# SM3320-BATT-EV.net
KiCad netlist of a schematic drawn in Altium Designer
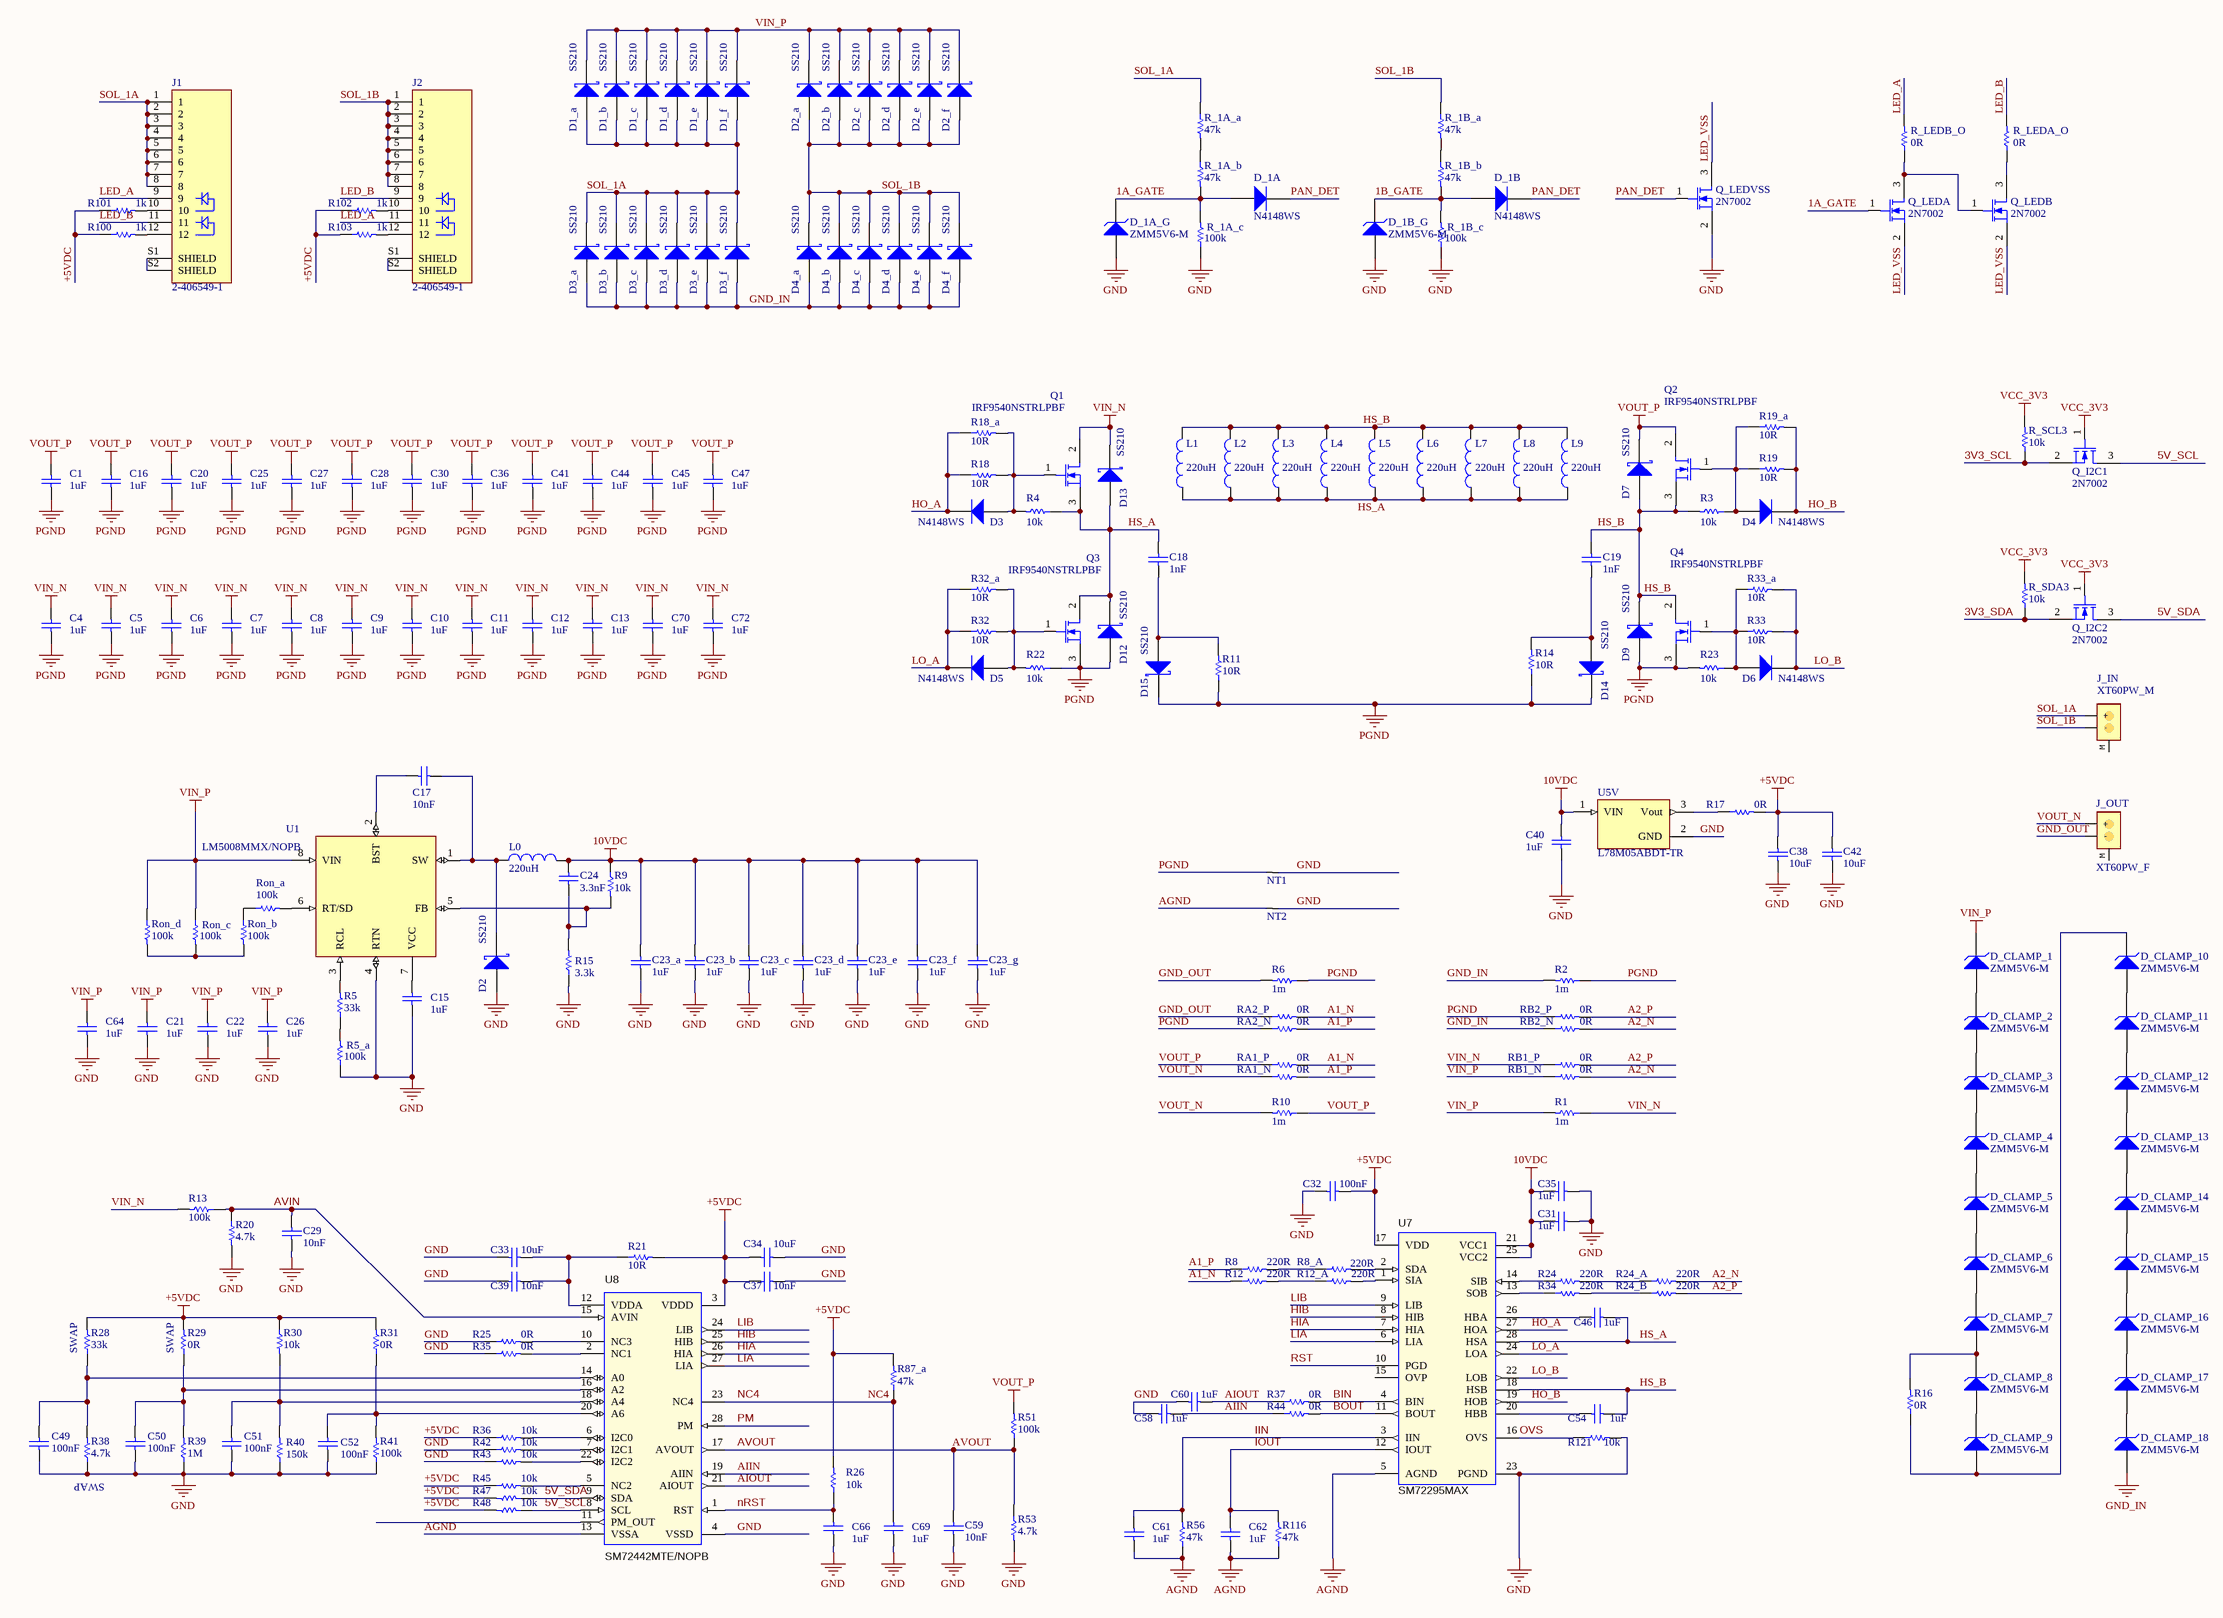
[diagram p0: SM3320-BATT-EV.SchDoc]

(export (version "E")
  (design (tool "Eeschema 10.0.6"))
  (components
    (comp (ref "C1")
      (value "1uF")
      (footprint "C_1206")
      (description "C - CAPACITOR - MLCC - 1uF - 100V - 1206 - X7R")
      (fields (field (name "LCSC PART #") "C91151") (field (name "Comment") "1206B105K101NT"))
      (libsource (lib "JLC_PCB") (part "1206B105K101NT"))
    )
    (comp (ref "C4")
      (value "1uF")
      (footprint "C_1206")
      (description "C - CAPACITOR - MLCC - 1uF - 100V - 1206 - X7R")
      (fields (field (name "LCSC PART #") "C91151") (field (name "Comment") "1206B105K101NT"))
      (libsource (lib "JLC_PCB") (part "1206B105K101NT"))
    )
    (comp (ref "C5")
      (value "1uF")
      (footprint "C_1206")
      (description "C - CAPACITOR - MLCC - 1uF - 100V - 1206 - X7R")
      (fields (field (name "LCSC PART #") "C91151") (field (name "Comment") "1206B105K101NT"))
      (libsource (lib "JLC_PCB") (part "1206B105K101NT"))
    )
    (comp (ref "C6")
      (value "1uF")
      (footprint "C_1206")
      (description "C - CAPACITOR - MLCC - 1uF - 100V - 1206 - X7R")
      (fields (field (name "LCSC PART #") "C91151") (field (name "Comment") "1206B105K101NT"))
      (libsource (lib "JLC_PCB") (part "1206B105K101NT"))
    )
    (comp (ref "C7")
      (value "1uF")
      (footprint "C_1206")
      (description "C - CAPACITOR - MLCC - 1uF - 100V - 1206 - X7R")
      (fields (field (name "LCSC PART #") "C91151") (field (name "Comment") "1206B105K101NT"))
      (libsource (lib "JLC_PCB") (part "1206B105K101NT"))
    )
    (comp (ref "C8")
      (value "1uF")
      (footprint "C_1206")
      (description "C - CAPACITOR - MLCC - 1uF - 100V - 1206 - X7R")
      (fields (field (name "LCSC PART #") "C91151") (field (name "Comment") "1206B105K101NT"))
      (libsource (lib "JLC_PCB") (part "1206B105K101NT"))
    )
    (comp (ref "C9")
      (value "1uF")
      (footprint "C_1206")
      (description "C - CAPACITOR - MLCC - 1uF - 100V - 1206 - X7R")
      (fields (field (name "LCSC PART #") "C91151") (field (name "Comment") "1206B105K101NT"))
      (libsource (lib "JLC_PCB") (part "1206B105K101NT"))
    )
    (comp (ref "C10")
      (value "1uF")
      (footprint "C_1206")
      (description "C - CAPACITOR - MLCC - 1uF - 100V - 1206 - X7R")
      (fields (field (name "LCSC PART #") "C91151") (field (name "Comment") "1206B105K101NT"))
      (libsource (lib "JLC_PCB") (part "1206B105K101NT"))
    )
    (comp (ref "C11")
      (value "1uF")
      (footprint "C_1206")
      (description "C - CAPACITOR - MLCC - 1uF - 100V - 1206 - X7R")
      (fields (field (name "LCSC PART #") "C91151") (field (name "Comment") "1206B105K101NT"))
      (libsource (lib "JLC_PCB") (part "1206B105K101NT"))
    )
    (comp (ref "C12")
      (value "1uF")
      (footprint "C_1206")
      (description "C - CAPACITOR - MLCC - 1uF - 100V - 1206 - X7R")
      (fields (field (name "LCSC PART #") "C91151") (field (name "Comment") "1206B105K101NT"))
      (libsource (lib "JLC_PCB") (part "1206B105K101NT"))
    )
    (comp (ref "C13")
      (value "1uF")
      (footprint "C_1206")
      (description "C - CAPACITOR - MLCC - 1uF - 100V - 1206 - X7R")
      (fields (field (name "LCSC PART #") "C91151") (field (name "Comment") "1206B105K101NT"))
      (libsource (lib "JLC_PCB") (part "1206B105K101NT"))
    )
    (comp (ref "C15")
      (value "1uF")
      (footprint "C_0402")
      (description "C - CAPACITOR - MLCC - 1uF - 25V - 0402")
      (fields (field (name "LCSC PART #") "C52923") (field (name "Comment") "CL05A105KA5NQNC"))
      (libsource (lib "JLC_PCB") (part "CL05A105KA5NQNC"))
    )
    (comp (ref "C16")
      (value "1uF")
      (footprint "C_1206")
      (description "C - CAPACITOR - MLCC - 1uF - 100V - 1206 - X7R")
      (fields (field (name "LCSC PART #") "C91151") (field (name "Comment") "1206B105K101NT"))
      (libsource (lib "JLC_PCB") (part "1206B105K101NT"))
    )
    (comp (ref "C17")
      (value "10nF")
      (footprint "C_0402")
      (description "C - CAPACITOR - MLCC - 10nF - 50V - 0402")
      (fields (field (name "LCSC PART #") "C15195") (field (name "Comment") "CL05B103KB5NNNC"))
      (libsource (lib "JLC_PCB") (part "CL05B103KB5NNNC"))
    )
    (comp (ref "C18")
      (value "1nF")
      (footprint "C_1206")
      (description "C - CAPACITOR - MLCC - 1nF - 2000V - 1206 - X7R")
      (fields (field (name "LCSC PART #") "C9196") (field (name "Comment") "1206B102K202NT"))
      (libsource (lib "JLC_PCB") (part "1206B102K202NT"))
    )
    (comp (ref "C19")
      (value "1nF")
      (footprint "C_1206")
      (description "C - CAPACITOR - MLCC - 1nF - 2000V - 1206 - X7R")
      (fields (field (name "LCSC PART #") "C9196") (field (name "Comment") "1206B102K202NT"))
      (libsource (lib "JLC_PCB") (part "1206B102K202NT"))
    )
    (comp (ref "C20")
      (value "1uF")
      (footprint "C_1206")
      (description "C - CAPACITOR - MLCC - 1uF - 100V - 1206 - X7R")
      (fields (field (name "LCSC PART #") "C91151") (field (name "Comment") "1206B105K101NT"))
      (libsource (lib "JLC_PCB") (part "1206B105K101NT"))
    )
    (comp (ref "C21")
      (value "1uF")
      (footprint "C_1206")
      (description "C - CAPACITOR - MLCC - 1uF - 100V - 1206 - X7R")
      (fields (field (name "LCSC PART #") "C91151") (field (name "Comment") "1206B105K101NT"))
      (libsource (lib "JLC_PCB") (part "1206B105K101NT"))
    )
    (comp (ref "C22")
      (value "1uF")
      (footprint "C_1206")
      (description "C - CAPACITOR - MLCC - 1uF - 100V - 1206 - X7R")
      (fields (field (name "LCSC PART #") "C91151") (field (name "Comment") "1206B105K101NT"))
      (libsource (lib "JLC_PCB") (part "1206B105K101NT"))
    )
    (comp (ref "C23_a")
      (value "1uF")
      (footprint "C_0402")
      (description "C - CAPACITOR - MLCC - 1uF - 25V - 0402")
      (fields (field (name "LCSC PART #") "C52923") (field (name "Comment") "CL05A105KA5NQNC"))
      (libsource (lib "JLC_PCB") (part "CL05A105KA5NQNC"))
    )
    (comp (ref "C23_b")
      (value "1uF")
      (footprint "C_0402")
      (description "C - CAPACITOR - MLCC - 1uF - 25V - 0402")
      (fields (field (name "LCSC PART #") "C52923") (field (name "Comment") "CL05A105KA5NQNC"))
      (libsource (lib "JLC_PCB") (part "CL05A105KA5NQNC"))
    )
    (comp (ref "C23_c")
      (value "1uF")
      (footprint "C_0402")
      (description "C - CAPACITOR - MLCC - 1uF - 25V - 0402")
      (fields (field (name "LCSC PART #") "C52923") (field (name "Comment") "CL05A105KA5NQNC"))
      (libsource (lib "JLC_PCB") (part "CL05A105KA5NQNC"))
    )
    (comp (ref "C23_d")
      (value "1uF")
      (footprint "C_0402")
      (description "C - CAPACITOR - MLCC - 1uF - 25V - 0402")
      (fields (field (name "LCSC PART #") "C52923") (field (name "Comment") "CL05A105KA5NQNC"))
      (libsource (lib "JLC_PCB") (part "CL05A105KA5NQNC"))
    )
    (comp (ref "C23_e")
      (value "1uF")
      (footprint "C_0402")
      (description "C - CAPACITOR - MLCC - 1uF - 25V - 0402")
      (fields (field (name "LCSC PART #") "C52923") (field (name "Comment") "CL05A105KA5NQNC"))
      (libsource (lib "JLC_PCB") (part "CL05A105KA5NQNC"))
    )
    (comp (ref "C23_f")
      (value "1uF")
      (footprint "C_0402")
      (description "C - CAPACITOR - MLCC - 1uF - 25V - 0402")
      (fields (field (name "LCSC PART #") "C52923") (field (name "Comment") "CL05A105KA5NQNC"))
      (libsource (lib "JLC_PCB") (part "CL05A105KA5NQNC"))
    )
    (comp (ref "C23_g")
      (value "1uF")
      (footprint "C_0402")
      (description "C - CAPACITOR - MLCC - 1uF - 25V - 0402")
      (fields (field (name "LCSC PART #") "C52923") (field (name "Comment") "CL05A105KA5NQNC"))
      (libsource (lib "JLC_PCB") (part "CL05A105KA5NQNC"))
    )
    (comp (ref "C24")
      (value "3.3nF")
      (footprint "C_0402")
      (description "C - CAPACITOR - MLCC - 3.3nF - 50V - 0402")
      (fields (field (name "LCSC PART #") "C26404") (field (name "Comment") "CL05B332KB5NNNC"))
      (libsource (lib "JLC_PCB") (part "CL05B332KB5NNNC"))
    )
    (comp (ref "C25")
      (value "1uF")
      (footprint "C_1206")
      (description "C - CAPACITOR - MLCC - 1uF - 100V - 1206 - X7R")
      (fields (field (name "LCSC PART #") "C91151") (field (name "Comment") "1206B105K101NT"))
      (libsource (lib "JLC_PCB") (part "1206B105K101NT"))
    )
    (comp (ref "C26")
      (value "1uF")
      (footprint "C_1206")
      (description "C - CAPACITOR - MLCC - 1uF - 100V - 1206 - X7R")
      (fields (field (name "LCSC PART #") "C91151") (field (name "Comment") "1206B105K101NT"))
      (libsource (lib "JLC_PCB") (part "1206B105K101NT"))
    )
    (comp (ref "C27")
      (value "1uF")
      (footprint "C_1206")
      (description "C - CAPACITOR - MLCC - 1uF - 100V - 1206 - X7R")
      (fields (field (name "LCSC PART #") "C91151") (field (name "Comment") "1206B105K101NT"))
      (libsource (lib "JLC_PCB") (part "1206B105K101NT"))
    )
    (comp (ref "C28")
      (value "1uF")
      (footprint "C_1206")
      (description "C - CAPACITOR - MLCC - 1uF - 100V - 1206 - X7R")
      (fields (field (name "LCSC PART #") "C91151") (field (name "Comment") "1206B105K101NT"))
      (libsource (lib "JLC_PCB") (part "1206B105K101NT"))
    )
    (comp (ref "C29")
      (value "10nF")
      (footprint "C_0402")
      (description "C - CAPACITOR - MLCC - 10nF - 50V - 0402")
      (fields (field (name "LCSC PART #") "C15195") (field (name "Comment") "CL05B103KB5NNNC"))
      (libsource (lib "JLC_PCB") (part "CL05B103KB5NNNC"))
    )
    (comp (ref "C30")
      (value "1uF")
      (footprint "C_1206")
      (description "C - CAPACITOR - MLCC - 1uF - 100V - 1206 - X7R")
      (fields (field (name "LCSC PART #") "C91151") (field (name "Comment") "1206B105K101NT"))
      (libsource (lib "JLC_PCB") (part "1206B105K101NT"))
    )
    (comp (ref "C31")
      (value "1uF")
      (footprint "C_0402")
      (description "C - CAPACITOR - MLCC - 1uF - 25V - 0402")
      (fields (field (name "LCSC PART #") "C52923") (field (name "Comment") "CL05A105KA5NQNC"))
      (libsource (lib "JLC_PCB") (part "CL05A105KA5NQNC"))
    )
    (comp (ref "C32")
      (value "100nF")
      (footprint "C_0402")
      (description "C - CAPACITOR - MLCC - 100nF - 16V - 0402")
      (fields (field (name "LCSC PART #") "C1525") (field (name "Comment") "CL05B104KO5NNNC"))
      (libsource (lib "JLC_PCB") (part "CL05B104KO5NNNC"))
    )
    (comp (ref "C33")
      (value "10uF")
      (footprint "C_0402")
      (description "C - CAPACITOR - MLCC - 10uF - 6.3V - 0402")
      (fields (field (name "LCSC PART #") "C15525") (field (name "Comment") "CL05A106MQ5NUNC"))
      (libsource (lib "JLC_PCB") (part "CL05A106MQ5NUNC"))
    )
    (comp (ref "C34")
      (value "10uF")
      (footprint "C_0402")
      (description "C - CAPACITOR - MLCC - 10uF - 6.3V - 0402")
      (fields (field (name "LCSC PART #") "C15525") (field (name "Comment") "CL05A106MQ5NUNC"))
      (libsource (lib "JLC_PCB") (part "CL05A106MQ5NUNC"))
    )
    (comp (ref "C35")
      (value "1uF")
      (footprint "C_0402")
      (description "C - CAPACITOR - MLCC - 1uF - 25V - 0402")
      (fields (field (name "LCSC PART #") "C52923") (field (name "Comment") "CL05A105KA5NQNC"))
      (libsource (lib "JLC_PCB") (part "CL05A105KA5NQNC"))
    )
    (comp (ref "C36")
      (value "1uF")
      (footprint "C_1206")
      (description "C - CAPACITOR - MLCC - 1uF - 100V - 1206 - X7R")
      (fields (field (name "LCSC PART #") "C91151") (field (name "Comment") "1206B105K101NT"))
      (libsource (lib "JLC_PCB") (part "1206B105K101NT"))
    )
    (comp (ref "C37")
      (value "10nF")
      (footprint "C_0402")
      (description "C - CAPACITOR - MLCC - 10nF - 50V - 0402")
      (fields (field (name "LCSC PART #") "C15195") (field (name "Comment") "CL05B103KB5NNNC"))
      (libsource (lib "JLC_PCB") (part "CL05B103KB5NNNC"))
    )
    (comp (ref "C38")
      (value "10uF")
      (footprint "C_0402")
      (description "C - CAPACITOR - MLCC - 10uF - 6.3V - 0402")
      (fields (field (name "LCSC PART #") "C15525") (field (name "Comment") "CL05A106MQ5NUNC"))
      (libsource (lib "JLC_PCB") (part "CL05A106MQ5NUNC"))
    )
    (comp (ref "C39")
      (value "10nF")
      (footprint "C_0402")
      (description "C - CAPACITOR - MLCC - 10nF - 50V - 0402")
      (fields (field (name "LCSC PART #") "C15195") (field (name "Comment") "CL05B103KB5NNNC"))
      (libsource (lib "JLC_PCB") (part "CL05B103KB5NNNC"))
    )
    (comp (ref "C40")
      (value "1uF")
      (footprint "C_0402")
      (description "C - CAPACITOR - MLCC - 1uF - 25V - 0402")
      (fields (field (name "LCSC PART #") "C52923") (field (name "Comment") "CL05A105KA5NQNC"))
      (libsource (lib "JLC_PCB") (part "CL05A105KA5NQNC"))
    )
    (comp (ref "C41")
      (value "1uF")
      (footprint "C_1206")
      (description "C - CAPACITOR - MLCC - 1uF - 100V - 1206 - X7R")
      (fields (field (name "LCSC PART #") "C91151") (field (name "Comment") "1206B105K101NT"))
      (libsource (lib "JLC_PCB") (part "1206B105K101NT"))
    )
    (comp (ref "C42")
      (value "10uF")
      (footprint "C_0402")
      (description "C - CAPACITOR - MLCC - 10uF - 6.3V - 0402")
      (fields (field (name "LCSC PART #") "C15525") (field (name "Comment") "CL05A106MQ5NUNC"))
      (libsource (lib "JLC_PCB") (part "CL05A106MQ5NUNC"))
    )
    (comp (ref "C44")
      (value "1uF")
      (footprint "C_1206")
      (description "C - CAPACITOR - MLCC - 1uF - 100V - 1206 - X7R")
      (fields (field (name "LCSC PART #") "C91151") (field (name "Comment") "1206B105K101NT"))
      (libsource (lib "JLC_PCB") (part "1206B105K101NT"))
    )
    (comp (ref "C45")
      (value "1uF")
      (footprint "C_1206")
      (description "C - CAPACITOR - MLCC - 1uF - 100V - 1206 - X7R")
      (fields (field (name "LCSC PART #") "C91151") (field (name "Comment") "1206B105K101NT"))
      (libsource (lib "JLC_PCB") (part "1206B105K101NT"))
    )
    (comp (ref "C46")
      (value "1uF")
      (footprint "C_0402")
      (description "C - CAPACITOR - MLCC - 1uF - 25V - 0402")
      (fields (field (name "LCSC PART #") "C52923") (field (name "Comment") "CL05A105KA5NQNC"))
      (libsource (lib "JLC_PCB") (part "CL05A105KA5NQNC"))
    )
    (comp (ref "C47")
      (value "1uF")
      (footprint "C_1206")
      (description "C - CAPACITOR - MLCC - 1uF - 100V - 1206 - X7R")
      (fields (field (name "LCSC PART #") "C91151") (field (name "Comment") "1206B105K101NT"))
      (libsource (lib "JLC_PCB") (part "1206B105K101NT"))
    )
    (comp (ref "C49")
      (value "100nF")
      (footprint "C_0402")
      (description "C - CAPACITOR - MLCC - 100nF - 16V - 0402")
      (fields (field (name "LCSC PART #") "C1525") (field (name "Comment") "CL05B104KO5NNNC"))
      (libsource (lib "JLC_PCB") (part "CL05B104KO5NNNC"))
    )
    (comp (ref "C50")
      (value "100nF")
      (footprint "C_0402")
      (description "C - CAPACITOR - MLCC - 100nF - 16V - 0402")
      (fields (field (name "LCSC PART #") "C1525") (field (name "Comment") "CL05B104KO5NNNC"))
      (libsource (lib "JLC_PCB") (part "CL05B104KO5NNNC"))
    )
    (comp (ref "C51")
      (value "100nF")
      (footprint "C_0402")
      (description "C - CAPACITOR - MLCC - 100nF - 16V - 0402")
      (fields (field (name "LCSC PART #") "C1525") (field (name "Comment") "CL05B104KO5NNNC"))
      (libsource (lib "JLC_PCB") (part "CL05B104KO5NNNC"))
    )
    (comp (ref "C52")
      (value "100nF")
      (footprint "C_0402")
      (description "C - CAPACITOR - MLCC - 100nF - 16V - 0402")
      (fields (field (name "LCSC PART #") "C1525") (field (name "Comment") "CL05B104KO5NNNC"))
      (libsource (lib "JLC_PCB") (part "CL05B104KO5NNNC"))
    )
    (comp (ref "C54")
      (value "1uF")
      (footprint "C_0402")
      (description "C - CAPACITOR - MLCC - 1uF - 25V - 0402")
      (fields (field (name "LCSC PART #") "C52923") (field (name "Comment") "CL05A105KA5NQNC"))
      (libsource (lib "JLC_PCB") (part "CL05A105KA5NQNC"))
    )
    (comp (ref "C58")
      (value "1uF")
      (footprint "C_0402")
      (description "C - CAPACITOR - MLCC - 1uF - 25V - 0402")
      (fields (field (name "LCSC PART #") "C52923") (field (name "Comment") "CL05A105KA5NQNC"))
      (libsource (lib "JLC_PCB") (part "CL05A105KA5NQNC"))
    )
    (comp (ref "C59")
      (value "10nF")
      (footprint "C_0402")
      (description "C - CAPACITOR - MLCC - 10nF - 50V - 0402")
      (fields (field (name "LCSC PART #") "C15195") (field (name "Comment") "CL05B103KB5NNNC"))
      (libsource (lib "JLC_PCB") (part "CL05B103KB5NNNC"))
    )
    (comp (ref "C60")
      (value "1uF")
      (footprint "C_0402")
      (description "C - CAPACITOR - MLCC - 1uF - 25V - 0402")
      (fields (field (name "LCSC PART #") "C52923") (field (name "Comment") "CL05A105KA5NQNC"))
      (libsource (lib "JLC_PCB") (part "CL05A105KA5NQNC"))
    )
    (comp (ref "C61")
      (value "1uF")
      (footprint "C_0402")
      (description "C - CAPACITOR - MLCC - 1uF - 25V - 0402")
      (fields (field (name "LCSC PART #") "C52923") (field (name "Comment") "CL05A105KA5NQNC"))
      (libsource (lib "JLC_PCB") (part "CL05A105KA5NQNC"))
    )
    (comp (ref "C62")
      (value "1uF")
      (footprint "C_0402")
      (description "C - CAPACITOR - MLCC - 1uF - 25V - 0402")
      (fields (field (name "LCSC PART #") "C52923") (field (name "Comment") "CL05A105KA5NQNC"))
      (libsource (lib "JLC_PCB") (part "CL05A105KA5NQNC"))
    )
    (comp (ref "C64")
      (value "1uF")
      (footprint "C_1206")
      (description "C - CAPACITOR - MLCC - 1uF - 100V - 1206 - X7R")
      (fields (field (name "LCSC PART #") "C91151") (field (name "Comment") "1206B105K101NT"))
      (libsource (lib "JLC_PCB") (part "1206B105K101NT"))
    )
    (comp (ref "C66")
      (value "1uF")
      (footprint "C_0402")
      (description "C - CAPACITOR - MLCC - 1uF - 25V - 0402")
      (fields (field (name "LCSC PART #") "C52923") (field (name "Comment") "CL05A105KA5NQNC"))
      (libsource (lib "JLC_PCB") (part "CL05A105KA5NQNC"))
    )
    (comp (ref "C69")
      (value "1uF")
      (footprint "C_0402")
      (description "C - CAPACITOR - MLCC - 1uF - 25V - 0402")
      (fields (field (name "LCSC PART #") "C52923") (field (name "Comment") "CL05A105KA5NQNC"))
      (libsource (lib "JLC_PCB") (part "CL05A105KA5NQNC"))
    )
    (comp (ref "C70")
      (value "1uF")
      (footprint "C_1206")
      (description "C - CAPACITOR - MLCC - 1uF - 100V - 1206 - X7R")
      (fields (field (name "LCSC PART #") "C91151") (field (name "Comment") "1206B105K101NT"))
      (libsource (lib "JLC_PCB") (part "1206B105K101NT"))
    )
    (comp (ref "C72")
      (value "1uF")
      (footprint "C_1206")
      (description "C - CAPACITOR - MLCC - 1uF - 100V - 1206 - X7R")
      (fields (field (name "LCSC PART #") "C91151") (field (name "Comment") "1206B105K101NT"))
      (libsource (lib "JLC_PCB") (part "1206B105K101NT"))
    )
    (comp (ref "D1_a")
      (value "SS210")
      (footprint "DO-214AC")
      (description "D - DIODE - SCHOTTKY - 100V - 2A")
      (fields (field (name "LCSC PART #") "C14996"))
      (libsource (lib "JLC_PCB") (part "SS210"))
    )
    (comp (ref "D1_b")
      (value "SS210")
      (footprint "DO-214AC")
      (description "D - DIODE - SCHOTTKY - 100V - 2A")
      (fields (field (name "LCSC PART #") "C14996"))
      (libsource (lib "JLC_PCB") (part "SS210"))
    )
    (comp (ref "D1_c")
      (value "SS210")
      (footprint "DO-214AC")
      (description "D - DIODE - SCHOTTKY - 100V - 2A")
      (fields (field (name "LCSC PART #") "C14996"))
      (libsource (lib "JLC_PCB") (part "SS210"))
    )
    (comp (ref "D1_d")
      (value "SS210")
      (footprint "DO-214AC")
      (description "D - DIODE - SCHOTTKY - 100V - 2A")
      (fields (field (name "LCSC PART #") "C14996"))
      (libsource (lib "JLC_PCB") (part "SS210"))
    )
    (comp (ref "D1_e")
      (value "SS210")
      (footprint "DO-214AC")
      (description "D - DIODE - SCHOTTKY - 100V - 2A")
      (fields (field (name "LCSC PART #") "C14996"))
      (libsource (lib "JLC_PCB") (part "SS210"))
    )
    (comp (ref "D1_f")
      (value "SS210")
      (footprint "DO-214AC")
      (description "D - DIODE - SCHOTTKY - 100V - 2A")
      (fields (field (name "LCSC PART #") "C14996"))
      (libsource (lib "JLC_PCB") (part "SS210"))
    )
    (comp (ref "D2")
      (value "SS210")
      (footprint "DO-214AC")
      (description "D - DIODE - SCHOTTKY - 100V - 2A")
      (fields (field (name "LCSC PART #") "C14996"))
      (libsource (lib "JLC_PCB") (part "SS210"))
    )
    (comp (ref "D2_a")
      (value "SS210")
      (footprint "DO-214AC")
      (description "D - DIODE - SCHOTTKY - 100V - 2A")
      (fields (field (name "LCSC PART #") "C14996"))
      (libsource (lib "JLC_PCB") (part "SS210"))
    )
    (comp (ref "D2_b")
      (value "SS210")
      (footprint "DO-214AC")
      (description "D - DIODE - SCHOTTKY - 100V - 2A")
      (fields (field (name "LCSC PART #") "C14996"))
      (libsource (lib "JLC_PCB") (part "SS210"))
    )
    (comp (ref "D2_c")
      (value "SS210")
      (footprint "DO-214AC")
      (description "D - DIODE - SCHOTTKY - 100V - 2A")
      (fields (field (name "LCSC PART #") "C14996"))
      (libsource (lib "JLC_PCB") (part "SS210"))
    )
    (comp (ref "D2_d")
      (value "SS210")
      (footprint "DO-214AC")
      (description "D - DIODE - SCHOTTKY - 100V - 2A")
      (fields (field (name "LCSC PART #") "C14996"))
      (libsource (lib "JLC_PCB") (part "SS210"))
    )
    (comp (ref "D2_e")
      (value "SS210")
      (footprint "DO-214AC")
      (description "D - DIODE - SCHOTTKY - 100V - 2A")
      (fields (field (name "LCSC PART #") "C14996"))
      (libsource (lib "JLC_PCB") (part "SS210"))
    )
    (comp (ref "D2_f")
      (value "SS210")
      (footprint "DO-214AC")
      (description "D - DIODE - SCHOTTKY - 100V - 2A")
      (fields (field (name "LCSC PART #") "C14996"))
      (libsource (lib "JLC_PCB") (part "SS210"))
    )
    (comp (ref "D3")
      (value "N4148WS")
      (footprint "SOD-323")
      (description "D - DIODE - FAST TRR - 100V - 150mA - 4ns")
      (fields (field (name "LCSC PART #") "C2128"))
      (libsource (lib "JLC_PCB") (part "N4148WS"))
    )
    (comp (ref "D3_a")
      (value "SS210")
      (footprint "DO-214AC")
      (description "D - DIODE - SCHOTTKY - 100V - 2A")
      (fields (field (name "LCSC PART #") "C14996"))
      (libsource (lib "JLC_PCB") (part "SS210"))
    )
    (comp (ref "D3_b")
      (value "SS210")
      (footprint "DO-214AC")
      (description "D - DIODE - SCHOTTKY - 100V - 2A")
      (fields (field (name "LCSC PART #") "C14996"))
      (libsource (lib "JLC_PCB") (part "SS210"))
    )
    (comp (ref "D3_c")
      (value "SS210")
      (footprint "DO-214AC")
      (description "D - DIODE - SCHOTTKY - 100V - 2A")
      (fields (field (name "LCSC PART #") "C14996"))
      (libsource (lib "JLC_PCB") (part "SS210"))
    )
    (comp (ref "D3_d")
      (value "SS210")
      (footprint "DO-214AC")
      (description "D - DIODE - SCHOTTKY - 100V - 2A")
      (fields (field (name "LCSC PART #") "C14996"))
      (libsource (lib "JLC_PCB") (part "SS210"))
    )
    (comp (ref "D3_e")
      (value "SS210")
      (footprint "DO-214AC")
      (description "D - DIODE - SCHOTTKY - 100V - 2A")
      (fields (field (name "LCSC PART #") "C14996"))
      (libsource (lib "JLC_PCB") (part "SS210"))
    )
    (comp (ref "D3_f")
      (value "SS210")
      (footprint "DO-214AC")
      (description "D - DIODE - SCHOTTKY - 100V - 2A")
      (fields (field (name "LCSC PART #") "C14996"))
      (libsource (lib "JLC_PCB") (part "SS210"))
    )
    (comp (ref "D4")
      (value "N4148WS")
      (footprint "SOD-323")
      (description "D - DIODE - FAST TRR - 100V - 150mA - 4ns")
      (fields (field (name "LCSC PART #") "C2128"))
      (libsource (lib "JLC_PCB") (part "N4148WS"))
    )
    (comp (ref "D4_a")
      (value "SS210")
      (footprint "DO-214AC")
      (description "D - DIODE - SCHOTTKY - 100V - 2A")
      (fields (field (name "LCSC PART #") "C14996"))
      (libsource (lib "JLC_PCB") (part "SS210"))
    )
    (comp (ref "D4_b")
      (value "SS210")
      (footprint "DO-214AC")
      (description "D - DIODE - SCHOTTKY - 100V - 2A")
      (fields (field (name "LCSC PART #") "C14996"))
      (libsource (lib "JLC_PCB") (part "SS210"))
    )
    (comp (ref "D4_c")
      (value "SS210")
      (footprint "DO-214AC")
      (description "D - DIODE - SCHOTTKY - 100V - 2A")
      (fields (field (name "LCSC PART #") "C14996"))
      (libsource (lib "JLC_PCB") (part "SS210"))
    )
    (comp (ref "D4_d")
      (value "SS210")
      (footprint "DO-214AC")
      (description "D - DIODE - SCHOTTKY - 100V - 2A")
      (fields (field (name "LCSC PART #") "C14996"))
      (libsource (lib "JLC_PCB") (part "SS210"))
    )
    (comp (ref "D4_e")
      (value "SS210")
      (footprint "DO-214AC")
      (description "D - DIODE - SCHOTTKY - 100V - 2A")
      (fields (field (name "LCSC PART #") "C14996"))
      (libsource (lib "JLC_PCB") (part "SS210"))
    )
    (comp (ref "D4_f")
      (value "SS210")
      (footprint "DO-214AC")
      (description "D - DIODE - SCHOTTKY - 100V - 2A")
      (fields (field (name "LCSC PART #") "C14996"))
      (libsource (lib "JLC_PCB") (part "SS210"))
    )
    (comp (ref "D5")
      (value "N4148WS")
      (footprint "SOD-323")
      (description "D - DIODE - FAST TRR - 100V - 150mA - 4ns")
      (fields (field (name "LCSC PART #") "C2128"))
      (libsource (lib "JLC_PCB") (part "N4148WS"))
    )
    (comp (ref "D6")
      (value "N4148WS")
      (footprint "SOD-323")
      (description "D - DIODE - FAST TRR - 100V - 150mA - 4ns")
      (fields (field (name "LCSC PART #") "C2128"))
      (libsource (lib "JLC_PCB") (part "N4148WS"))
    )
    (comp (ref "D7")
      (value "SS210")
      (footprint "DO-214AC")
      (description "D - DIODE - SCHOTTKY - 100V - 2A")
      (fields (field (name "LCSC PART #") "C14996"))
      (libsource (lib "JLC_PCB") (part "SS210"))
    )
    (comp (ref "D9")
      (value "SS210")
      (footprint "DO-214AC")
      (description "D - DIODE - SCHOTTKY - 100V - 2A")
      (fields (field (name "LCSC PART #") "C14996"))
      (libsource (lib "JLC_PCB") (part "SS210"))
    )
    (comp (ref "D12")
      (value "SS210")
      (footprint "DO-214AC")
      (description "D - DIODE - SCHOTTKY - 100V - 2A")
      (fields (field (name "LCSC PART #") "C14996"))
      (libsource (lib "JLC_PCB") (part "SS210"))
    )
    (comp (ref "D13")
      (value "SS210")
      (footprint "DO-214AC")
      (description "D - DIODE - SCHOTTKY - 100V - 2A")
      (fields (field (name "LCSC PART #") "C14996"))
      (libsource (lib "JLC_PCB") (part "SS210"))
    )
    (comp (ref "D14")
      (value "SS210")
      (footprint "DO-214AC")
      (description "D - DIODE - SCHOTTKY - 100V - 2A")
      (fields (field (name "LCSC PART #") "C14996"))
      (libsource (lib "JLC_PCB") (part "SS210"))
    )
    (comp (ref "D15")
      (value "SS210")
      (footprint "DO-214AC")
      (description "D - DIODE - SCHOTTKY - 100V - 2A")
      (fields (field (name "LCSC PART #") "C14996"))
      (libsource (lib "JLC_PCB") (part "SS210"))
    )
    (comp (ref "D_1A")
      (value "N4148WS")
      (footprint "SOD-323")
      (description "D - DIODE - FAST TRR - 100V - 150mA - 4ns")
      (fields (field (name "LCSC PART #") "C2128"))
      (libsource (lib "JLC_PCB") (part "N4148WS"))
    )
    (comp (ref "D_1A_G")
      (value "ZMM5V6-M")
      (footprint "DO-213AA")
      (description "D - DIODE - ZENER - 5.6V - 500mW")
      (fields (field (name "LCSC PART #") "C8062"))
      (libsource (lib "JLC_PCB") (part "ZMM5V6-M"))
    )
    (comp (ref "D_1B")
      (value "N4148WS")
      (footprint "SOD-323")
      (description "D - DIODE - FAST TRR - 100V - 150mA - 4ns")
      (fields (field (name "LCSC PART #") "C2128"))
      (libsource (lib "JLC_PCB") (part "N4148WS"))
    )
    (comp (ref "D_1B_G")
      (value "ZMM5V6-M")
      (footprint "DO-213AA")
      (description "D - DIODE - ZENER - 5.6V - 500mW")
      (fields (field (name "LCSC PART #") "C8062"))
      (libsource (lib "JLC_PCB") (part "ZMM5V6-M"))
    )
    (comp (ref "D_CLAMP_1")
      (value "ZMM5V6-M")
      (footprint "DO-213AA")
      (description "D - DIODE - ZENER - 5.6V - 500mW")
      (fields (field (name "LCSC PART #") "C8062"))
      (libsource (lib "JLC_PCB") (part "ZMM5V6-M"))
    )
    (comp (ref "D_CLAMP_2")
      (value "ZMM5V6-M")
      (footprint "DO-213AA")
      (description "D - DIODE - ZENER - 5.6V - 500mW")
      (fields (field (name "LCSC PART #") "C8062"))
      (libsource (lib "JLC_PCB") (part "ZMM5V6-M"))
    )
    (comp (ref "D_CLAMP_3")
      (value "ZMM5V6-M")
      (footprint "DO-213AA")
      (description "D - DIODE - ZENER - 5.6V - 500mW")
      (fields (field (name "LCSC PART #") "C8062"))
      (libsource (lib "JLC_PCB") (part "ZMM5V6-M"))
    )
    (comp (ref "D_CLAMP_4")
      (value "ZMM5V6-M")
      (footprint "DO-213AA")
      (description "D - DIODE - ZENER - 5.6V - 500mW")
      (fields (field (name "LCSC PART #") "C8062"))
      (libsource (lib "JLC_PCB") (part "ZMM5V6-M"))
    )
    (comp (ref "D_CLAMP_5")
      (value "ZMM5V6-M")
      (footprint "DO-213AA")
      (description "D - DIODE - ZENER - 5.6V - 500mW")
      (fields (field (name "LCSC PART #") "C8062"))
      (libsource (lib "JLC_PCB") (part "ZMM5V6-M"))
    )
    (comp (ref "D_CLAMP_6")
      (value "ZMM5V6-M")
      (footprint "DO-213AA")
      (description "D - DIODE - ZENER - 5.6V - 500mW")
      (fields (field (name "LCSC PART #") "C8062"))
      (libsource (lib "JLC_PCB") (part "ZMM5V6-M"))
    )
    (comp (ref "D_CLAMP_7")
      (value "ZMM5V6-M")
      (footprint "DO-213AA")
      (description "D - DIODE - ZENER - 5.6V - 500mW")
      (fields (field (name "LCSC PART #") "C8062"))
      (libsource (lib "JLC_PCB") (part "ZMM5V6-M"))
    )
    (comp (ref "D_CLAMP_8")
      (value "ZMM5V6-M")
      (footprint "DO-213AA")
      (description "D - DIODE - ZENER - 5.6V - 500mW")
      (fields (field (name "LCSC PART #") "C8062"))
      (libsource (lib "JLC_PCB") (part "ZMM5V6-M"))
    )
    (comp (ref "D_CLAMP_9")
      (value "ZMM5V6-M")
      (footprint "DO-213AA")
      (description "D - DIODE - ZENER - 5.6V - 500mW")
      (fields (field (name "LCSC PART #") "C8062"))
      (libsource (lib "JLC_PCB") (part "ZMM5V6-M"))
    )
    (comp (ref "D_CLAMP_10")
      (value "ZMM5V6-M")
      (footprint "DO-213AA")
      (description "D - DIODE - ZENER - 5.6V - 500mW")
      (fields (field (name "LCSC PART #") "C8062"))
      (libsource (lib "JLC_PCB") (part "ZMM5V6-M"))
    )
    (comp (ref "D_CLAMP_11")
      (value "ZMM5V6-M")
      (footprint "DO-213AA")
      (description "D - DIODE - ZENER - 5.6V - 500mW")
      (fields (field (name "LCSC PART #") "C8062"))
      (libsource (lib "JLC_PCB") (part "ZMM5V6-M"))
    )
    (comp (ref "D_CLAMP_12")
      (value "ZMM5V6-M")
      (footprint "DO-213AA")
      (description "D - DIODE - ZENER - 5.6V - 500mW")
      (fields (field (name "LCSC PART #") "C8062"))
      (libsource (lib "JLC_PCB") (part "ZMM5V6-M"))
    )
    (comp (ref "D_CLAMP_13")
      (value "ZMM5V6-M")
      (footprint "DO-213AA")
      (description "D - DIODE - ZENER - 5.6V - 500mW")
      (fields (field (name "LCSC PART #") "C8062"))
      (libsource (lib "JLC_PCB") (part "ZMM5V6-M"))
    )
    (comp (ref "D_CLAMP_14")
      (value "ZMM5V6-M")
      (footprint "DO-213AA")
      (description "D - DIODE - ZENER - 5.6V - 500mW")
      (fields (field (name "LCSC PART #") "C8062"))
      (libsource (lib "JLC_PCB") (part "ZMM5V6-M"))
    )
    (comp (ref "D_CLAMP_15")
      (value "ZMM5V6-M")
      (footprint "DO-213AA")
      (description "D - DIODE - ZENER - 5.6V - 500mW")
      (fields (field (name "LCSC PART #") "C8062"))
      (libsource (lib "JLC_PCB") (part "ZMM5V6-M"))
    )
    (comp (ref "D_CLAMP_16")
      (value "ZMM5V6-M")
      (footprint "DO-213AA")
      (description "D - DIODE - ZENER - 5.6V - 500mW")
      (fields (field (name "LCSC PART #") "C8062"))
      (libsource (lib "JLC_PCB") (part "ZMM5V6-M"))
    )
    (comp (ref "D_CLAMP_17")
      (value "ZMM5V6-M")
      (footprint "DO-213AA")
      (description "D - DIODE - ZENER - 5.6V - 500mW")
      (fields (field (name "LCSC PART #") "C8062"))
      (libsource (lib "JLC_PCB") (part "ZMM5V6-M"))
    )
    (comp (ref "D_CLAMP_18")
      (value "ZMM5V6-M")
      (footprint "DO-213AA")
      (description "D - DIODE - ZENER - 5.6V - 500mW")
      (fields (field (name "LCSC PART #") "C8062"))
      (libsource (lib "JLC_PCB") (part "ZMM5V6-M"))
    )
    (comp (ref "J1")
      (value "2-406549-1")
      (footprint "TE_2-406549-1")
      (description "J - JACK - ETHERNET - Right - THT")
      (fields (field (name "LCSC PART #") "C125068"))
      (libsource (lib "JLC_PCB") (part "2-406549-1"))
    )
    (comp (ref "J2")
      (value "2-406549-1")
      (footprint "TE_2-406549-1")
      (description "J - JACK - ETHERNET - Right - THT")
      (fields (field (name "LCSC PART #") "C125068"))
      (libsource (lib "JLC_PCB") (part "2-406549-1"))
    )
    (comp (ref "J_IN")
      (value "XT60PW_M")
      (footprint "XT60PW_M")
      (description "J - JACK - POWER - XT60 - RIGHT - MALE")
      (fields (field (name "LCSC PART #") "X"))
      (libsource (lib "JLC_PCB") (part "XT60PW_M"))
    )
    (comp (ref "J_OUT")
      (value "XT60PW_F")
      (footprint "XT60PW_F")
      (description "J - JACK - POWER - XT60 - RIGHT - FEMALE")
      (fields (field (name "LCSC PART #") "X"))
      (libsource (lib "JLC_PCB") (part "XT60PW_F"))
    )
    (comp (ref "L0")
      (value "220uH")
      (footprint "SRR1260")
      (description "L - INDUCTOR - 220uH - 1.6A - 12.5mm")
      (fields (field (name "LCSC PART #") "C169380") (field (name "Comment") "SWRB1207S-221MT"))
      (libsource (lib "JLC_PCB") (part "SWRB1207S-221MT"))
    )
    (comp (ref "L1")
      (value "220uH")
      (footprint "SRR1260")
      (description "L - INDUCTOR - 220uH - 1.6A - 12.5mm")
      (fields (field (name "LCSC PART #") "C169380") (field (name "Comment") "SWRB1207S-221MT"))
      (libsource (lib "JLC_PCB") (part "SWRB1207S-221MT"))
    )
    (comp (ref "L2")
      (value "220uH")
      (footprint "SRR1260")
      (description "L - INDUCTOR - 220uH - 1.6A - 12.5mm")
      (fields (field (name "LCSC PART #") "C169380") (field (name "Comment") "SWRB1207S-221MT"))
      (libsource (lib "JLC_PCB") (part "SWRB1207S-221MT"))
    )
    (comp (ref "L3")
      (value "220uH")
      (footprint "SRR1260")
      (description "L - INDUCTOR - 220uH - 1.6A - 12.5mm")
      (fields (field (name "LCSC PART #") "C169380") (field (name "Comment") "SWRB1207S-221MT"))
      (libsource (lib "JLC_PCB") (part "SWRB1207S-221MT"))
    )
    (comp (ref "L4")
      (value "220uH")
      (footprint "SRR1260")
      (description "L - INDUCTOR - 220uH - 1.6A - 12.5mm")
      (fields (field (name "LCSC PART #") "C169380") (field (name "Comment") "SWRB1207S-221MT"))
      (libsource (lib "JLC_PCB") (part "SWRB1207S-221MT"))
    )
    (comp (ref "L5")
      (value "220uH")
      (footprint "SRR1260")
      (description "L - INDUCTOR - 220uH - 1.6A - 12.5mm")
      (fields (field (name "LCSC PART #") "C169380") (field (name "Comment") "SWRB1207S-221MT"))
      (libsource (lib "JLC_PCB") (part "SWRB1207S-221MT"))
    )
    (comp (ref "L6")
      (value "220uH")
      (footprint "SRR1260")
      (description "L - INDUCTOR - 220uH - 1.6A - 12.5mm")
      (fields (field (name "LCSC PART #") "C169380") (field (name "Comment") "SWRB1207S-221MT"))
      (libsource (lib "JLC_PCB") (part "SWRB1207S-221MT"))
    )
    (comp (ref "L7")
      (value "220uH")
      (footprint "SRR1260")
      (description "L - INDUCTOR - 220uH - 1.6A - 12.5mm")
      (fields (field (name "LCSC PART #") "C169380") (field (name "Comment") "SWRB1207S-221MT"))
      (libsource (lib "JLC_PCB") (part "SWRB1207S-221MT"))
    )
    (comp (ref "L8")
      (value "220uH")
      (footprint "SRR1260")
      (description "L - INDUCTOR - 220uH - 1.6A - 12.5mm")
      (fields (field (name "LCSC PART #") "C169380") (field (name "Comment") "SWRB1207S-221MT"))
      (libsource (lib "JLC_PCB") (part "SWRB1207S-221MT"))
    )
    (comp (ref "L9")
      (value "220uH")
      (footprint "SRR1260")
      (description "L - INDUCTOR - 220uH - 1.6A - 12.5mm")
      (fields (field (name "LCSC PART #") "C169380") (field (name "Comment") "SWRB1207S-221MT"))
      (libsource (lib "JLC_PCB") (part "SWRB1207S-221MT"))
    )
    (comp (ref "NT1")
      (value "0")
      (footprint "NET_TIE")
      (description "R - Net Tie")
      (libsource (lib "JLC_PCB") (part "NET_TIE"))
    )
    (comp (ref "NT2")
      (value "0")
      (footprint "NET_TIE")
      (description "R - Net Tie")
      (libsource (lib "JLC_PCB") (part "NET_TIE"))
    )
    (comp (ref "Q1")
      (value "IRF9540NSTRLPBF")
      (footprint "TO-263-3")
      (description "Q - TRANSISTOR - MOSFET (N) - 250V - 33A - 0.094R")
      (fields (field (name "LCSC PART #") "C33903"))
      (libsource (lib "JLC_PCB") (part "IRF9540NSTRLPBF"))
    )
    (comp (ref "Q2")
      (value "IRF9540NSTRLPBF")
      (footprint "TO-263-3")
      (description "Q - TRANSISTOR - MOSFET (N) - 250V - 33A - 0.094R")
      (fields (field (name "LCSC PART #") "C33903"))
      (libsource (lib "JLC_PCB") (part "IRF9540NSTRLPBF"))
    )
    (comp (ref "Q3")
      (value "IRF9540NSTRLPBF")
      (footprint "TO-263-3")
      (description "Q - TRANSISTOR - MOSFET (N) - 250V - 33A - 0.094R")
      (fields (field (name "LCSC PART #") "C33903"))
      (libsource (lib "JLC_PCB") (part "IRF9540NSTRLPBF"))
    )
    (comp (ref "Q4")
      (value "IRF9540NSTRLPBF")
      (footprint "TO-263-3")
      (description "Q - TRANSISTOR - MOSFET (N) - 250V - 33A - 0.094R")
      (fields (field (name "LCSC PART #") "C33903"))
      (libsource (lib "JLC_PCB") (part "IRF9540NSTRLPBF"))
    )
    (comp (ref "Q_I2C1")
      (value "2N7002")
      (footprint "TO-236AB")
      (description "Q - TRANSISTOR - MOSFET (N) - 60V - 200mW")
      (fields (field (name "LCSC PART #") "C8545"))
      (libsource (lib "JLC_PCB") (part "2N7002"))
    )
    (comp (ref "Q_I2C2")
      (value "2N7002")
      (footprint "TO-236AB")
      (description "Q - TRANSISTOR - MOSFET (N) - 60V - 200mW")
      (fields (field (name "LCSC PART #") "C8545"))
      (libsource (lib "JLC_PCB") (part "2N7002"))
    )
    (comp (ref "Q_LEDA")
      (value "2N7002")
      (footprint "TO-236AB")
      (description "Q - TRANSISTOR - MOSFET (N) - 60V - 200mW")
      (fields (field (name "LCSC PART #") "C8545"))
      (libsource (lib "JLC_PCB") (part "2N7002"))
    )
    (comp (ref "Q_LEDB")
      (value "2N7002")
      (footprint "TO-236AB")
      (description "Q - TRANSISTOR - MOSFET (N) - 60V - 200mW")
      (fields (field (name "LCSC PART #") "C8545"))
      (libsource (lib "JLC_PCB") (part "2N7002"))
    )
    (comp (ref "Q_LEDVSS")
      (value "2N7002")
      (footprint "TO-236AB")
      (description "Q - TRANSISTOR - MOSFET (N) - 60V - 200mW")
      (fields (field (name "LCSC PART #") "C8545"))
      (libsource (lib "JLC_PCB") (part "2N7002"))
    )
    (comp (ref "R1")
      (value "1m")
      (footprint "R_2512")
      (description "R - RESISTOR - SMD - 0.001R - 1% - 2512 - 2W - 50ppm/k")
      (fields (field (name "LCSC PART #") "C349153") (field (name "POWER") "2W"))
      (libsource (lib "JLC_PCB") (part "EWSL2512F1L00S9"))
    )
    (comp (ref "R2")
      (value "1m")
      (footprint "R_2512")
      (description "R - RESISTOR - SMD - 0.001R - 1% - 2512 - 2W - 50ppm/k")
      (fields (field (name "LCSC PART #") "C349153") (field (name "POWER") "2W"))
      (libsource (lib "JLC_PCB") (part "EWSL2512F1L00S9"))
    )
    (comp (ref "R3")
      (value "10k")
      (footprint "R_0402")
      (description "R - RESISTOR - SMD - 10k - 1% - 0402")
      (fields (field (name "LCSC PART #") "C25744") (field (name "Comment") "0402WGF1002TCE"))
      (libsource (lib "JLC_PCB") (part "0402WGF1002TCE"))
    )
    (comp (ref "R4")
      (value "10k")
      (footprint "R_0402")
      (description "R - RESISTOR - SMD - 10k - 1% - 0402")
      (fields (field (name "LCSC PART #") "C25744") (field (name "Comment") "0402WGF1002TCE"))
      (libsource (lib "JLC_PCB") (part "0402WGF1002TCE"))
    )
    (comp (ref "R5")
      (value "33k")
      (footprint "R_0402")
      (description "R - RESISTOR - SMD - 33k - 1% - 0402")
      (fields (field (name "LCSC PART #") "C25779") (field (name "Comment") "0402WGF3302TCE"))
      (libsource (lib "JLC_PCB") (part "0402WGF3302TCE"))
    )
    (comp (ref "R5_a")
      (value "100k")
      (footprint "R_0402")
      (description "R - RESISTOR - SMD - 100k - 1% -  0402")
      (fields (field (name "LCSC PART #") "C25741") (field (name "Comment") "0402WGF1003TCE"))
      (libsource (lib "JLC_PCB") (part "0402WGF1003TCE"))
    )
    (comp (ref "R6")
      (value "1m")
      (footprint "R_2512")
      (description "R - RESISTOR - SMD - 0.001R - 1% - 2512 - 2W - 50ppm/k")
      (fields (field (name "LCSC PART #") "C349153") (field (name "POWER") "2W"))
      (libsource (lib "JLC_PCB") (part "EWSL2512F1L00S9"))
    )
    (comp (ref "R8")
      (value "220R")
      (footprint "R_0402")
      (description "R - RESISTOR - SMD - 220R - 1% - 0402")
      (fields (field (name "LCSC PART #") "C25091") (field (name "Comment") "0402WGF2200TCE"))
      (libsource (lib "JLC_PCB") (part "0402WGF2200TCE"))
    )
    (comp (ref "R8_A")
      (value "220R")
      (footprint "R_0402")
      (description "R - RESISTOR - SMD - 220R - 1% - 0402")
      (fields (field (name "LCSC PART #") "C25091"))
      (libsource (lib "*") (part "0402WGF2200TCE"))
    )
    (comp (ref "R9")
      (value "10k")
      (footprint "R_0402")
      (description "R - RESISTOR - SMD - 10k - 1% - 0402")
      (fields (field (name "LCSC PART #") "C25744") (field (name "Comment") "0402WGF1002TCE"))
      (libsource (lib "JLC_PCB") (part "0402WGF1002TCE"))
    )
    (comp (ref "R10")
      (value "1m")
      (footprint "R_2512")
      (description "R - RESISTOR - SMD - 0.001R - 1% - 2512 - 2W - 50ppm/k")
      (fields (field (name "LCSC PART #") "C349153") (field (name "POWER") "2W"))
      (libsource (lib "JLC_PCB") (part "EWSL2512F1L00S9"))
    )
    (comp (ref "R11")
      (value "10R")
      (footprint "R_1206")
      (description "R - RESISTOR - SMD - 10R - 1% - 1206")
      (fields (field (name "LCSC PART #") "C17903") (field (name "Comment") "1206W4F100JT5E"))
      (libsource (lib "JLC_PCB") (part "1206W4F100JT5E"))
    )
    (comp (ref "R12")
      (value "220R")
      (footprint "R_0402")
      (description "R - RESISTOR - SMD - 220R - 1% - 0402")
      (fields (field (name "LCSC PART #") "C25091") (field (name "Comment") "0402WGF2200TCE"))
      (libsource (lib "JLC_PCB") (part "0402WGF2200TCE"))
    )
    (comp (ref "R12_A")
      (value "220R")
      (footprint "R_0402")
      (description "R - RESISTOR - SMD - 220R - 1% - 0402")
      (fields (field (name "LCSC PART #") "C25091") (field (name "Comment") "0402WGF2200TCE"))
      (libsource (lib "JLC_PCB") (part "0402WGF2200TCE"))
    )
    (comp (ref "R13")
      (value "100k")
      (footprint "R_0603")
      (description "R - RESISTOR - SMD - 100k - 1% -  0603")
      (fields (field (name "LCSC PART #") "C22936") (field (name "Comment") "0603WAF100KT5E"))
      (libsource (lib "JLC_PCB") (part "0603WAF100KT5E"))
    )
    (comp (ref "R14")
      (value "10R")
      (footprint "R_1206")
      (description "R - RESISTOR - SMD - 10R - 1% - 1206")
      (fields (field (name "LCSC PART #") "C17903") (field (name "Comment") "1206W4F100JT5E"))
      (libsource (lib "JLC_PCB") (part "1206W4F100JT5E"))
    )
    (comp (ref "R15")
      (value "3.3k")
      (footprint "R_0402")
      (description "R - RESISTOR - SMD - 3.3k - 1% - 0402")
      (fields (field (name "LCSC PART #") "C25890") (field (name "Comment") "0402WGF3301TCE"))
      (libsource (lib "JLC_PCB") (part "0402WGF3301TCE"))
    )
    (comp (ref "R16")
      (value "0R")
      (footprint "R_0402")
      (description "R - RESISTOR - SMD - 0R - 1% - 0402")
      (fields (field (name "LCSC PART #") "C17168") (field (name "Comment") "0402WGF0000TCE"))
      (libsource (lib "JLC_PCB") (part "0402WGF0000TCE"))
    )
    (comp (ref "R17")
      (value "0R")
      (footprint "R_0402")
      (description "R - RESISTOR - SMD - 0R - 1% - 0402")
      (fields (field (name "LCSC PART #") "C17168") (field (name "Comment") "0402WGF0000TCE"))
      (libsource (lib "JLC_PCB") (part "0402WGF0000TCE"))
    )
    (comp (ref "R18")
      (value "10R")
      (footprint "R_0402")
      (description "R - RESISTOR - SMD - 10R - 1% - 0402")
      (fields (field (name "LCSC PART #") "C25077") (field (name "Comment") "0402WGF100JTCE"))
      (libsource (lib "JLC_PCB") (part "0402WGF100JTCE"))
    )
    (comp (ref "R18_a")
      (value "10R")
      (footprint "R_0402")
      (description "R - RESISTOR - SMD - 10R - 1% - 0402")
      (fields (field (name "LCSC PART #") "C25077") (field (name "Comment") "0402WGF100JTCE"))
      (libsource (lib "JLC_PCB") (part "0402WGF100JTCE"))
    )
    (comp (ref "R19")
      (value "10R")
      (footprint "R_0402")
      (description "R - RESISTOR - SMD - 10R - 1% - 0402")
      (fields (field (name "LCSC PART #") "C25077") (field (name "Comment") "0402WGF100JTCE"))
      (libsource (lib "JLC_PCB") (part "0402WGF100JTCE"))
    )
    (comp (ref "R19_a")
      (value "10R")
      (footprint "R_0402")
      (description "R - RESISTOR - SMD - 10R - 1% - 0402")
      (fields (field (name "LCSC PART #") "C25077") (field (name "Comment") "0402WGF100JTCE"))
      (libsource (lib "JLC_PCB") (part "0402WGF100JTCE"))
    )
    (comp (ref "R20")
      (value "4.7k")
      (footprint "R_0402")
      (description "R - RESISTOR - SMD - 4.7k - 1% - 0402")
      (fields (field (name "LCSC PART #") "C25900") (field (name "Comment") "0402WGF4701TCE"))
      (libsource (lib "JLC_PCB") (part "0402WGF4701TCE"))
    )
    (comp (ref "R21")
      (value "10R")
      (footprint "R_0402")
      (description "R - RESISTOR - SMD - 10R - 1% - 0402")
      (fields (field (name "LCSC PART #") "C25077") (field (name "Comment") "0402WGF100JTCE"))
      (libsource (lib "JLC_PCB") (part "0402WGF100JTCE"))
    )
    (comp (ref "R22")
      (value "10k")
      (footprint "R_0402")
      (description "R - RESISTOR - SMD - 10k - 1% - 0402")
      (fields (field (name "LCSC PART #") "C25744") (field (name "Comment") "0402WGF1002TCE"))
      (libsource (lib "JLC_PCB") (part "0402WGF1002TCE"))
    )
    (comp (ref "R23")
      (value "10k")
      (footprint "R_0402")
      (description "R - RESISTOR - SMD - 10k - 1% - 0402")
      (fields (field (name "LCSC PART #") "C25744") (field (name "Comment") "0402WGF1002TCE"))
      (libsource (lib "JLC_PCB") (part "0402WGF1002TCE"))
    )
    (comp (ref "R24")
      (value "220R")
      (footprint "R_0402")
      (description "R - RESISTOR - SMD - 220R - 1% - 0402")
      (fields (field (name "LCSC PART #") "C25091") (field (name "Comment") "0402WGF2200TCE"))
      (libsource (lib "JLC_PCB") (part "0402WGF2200TCE"))
    )
    (comp (ref "R24_A")
      (value "220R")
      (footprint "R_0402")
      (description "R - RESISTOR - SMD - 220R - 1% - 0402")
      (fields (field (name "LCSC PART #") "C25091") (field (name "Comment") "0402WGF2200TCE"))
      (libsource (lib "JLC_PCB") (part "0402WGF2200TCE"))
    )
    (comp (ref "R24_B")
      (value "220R")
      (footprint "R_0402")
      (description "R - RESISTOR - SMD - 220R - 1% - 0402")
      (fields (field (name "LCSC PART #") "C25091") (field (name "Comment") "0402WGF2200TCE"))
      (libsource (lib "JLC_PCB") (part "0402WGF2200TCE"))
    )
    (comp (ref "R25")
      (value "0R")
      (footprint "R_0402")
      (description "R - RESISTOR - SMD - 0R - 1% - 0402")
      (fields (field (name "LCSC PART #") "C17168") (field (name "Comment") "0402WGF0000TCE"))
      (libsource (lib "JLC_PCB") (part "0402WGF0000TCE"))
    )
    (comp (ref "R26")
      (value "10k")
      (footprint "R_0402")
      (description "R - RESISTOR - SMD - 10k - 1% - 0402")
      (fields (field (name "LCSC PART #") "C25744") (field (name "Comment") "0402WGF1002TCE"))
      (libsource (lib "JLC_PCB") (part "0402WGF1002TCE"))
    )
    (comp (ref "R28")
      (value "33k")
      (footprint "R_0402")
      (description "R - RESISTOR - SMD - 33k - 1% - 0402")
      (fields (field (name "LCSC PART #") "C25779") (field (name "Comment") "0402WGF3302TCE"))
      (libsource (lib "JLC_PCB") (part "0402WGF3302TCE"))
    )
    (comp (ref "R29")
      (value "0R")
      (footprint "R_0402")
      (description "R - RESISTOR - SMD - 0R - 1% - 0402")
      (fields (field (name "LCSC PART #") "C17168") (field (name "Comment") "0402WGF0000TCE"))
      (libsource (lib "JLC_PCB") (part "0402WGF0000TCE"))
    )
    (comp (ref "R30")
      (value "10k")
      (footprint "R_0402")
      (description "R - RESISTOR - SMD - 10k - 1% - 0402")
      (fields (field (name "LCSC PART #") "C25744") (field (name "Comment") "0402WGF1002TCE"))
      (libsource (lib "JLC_PCB") (part "0402WGF1002TCE"))
    )
    (comp (ref "R31")
      (value "0R")
      (footprint "R_0402")
      (description "R - RESISTOR - SMD - 0R - 1% - 0402")
      (fields (field (name "LCSC PART #") "C17168") (field (name "Comment") "0402WGF0000TCE"))
      (libsource (lib "JLC_PCB") (part "0402WGF0000TCE"))
    )
    (comp (ref "R32")
      (value "10R")
      (footprint "R_0402")
      (description "R - RESISTOR - SMD - 10R - 1% - 0402")
      (fields (field (name "LCSC PART #") "C25077") (field (name "Comment") "0402WGF100JTCE"))
      (libsource (lib "JLC_PCB") (part "0402WGF100JTCE"))
    )
    (comp (ref "R32_a")
      (value "10R")
      (footprint "R_0402")
      (description "R - RESISTOR - SMD - 10R - 1% - 0402")
      (fields (field (name "LCSC PART #") "C25077") (field (name "Comment") "0402WGF100JTCE"))
      (libsource (lib "JLC_PCB") (part "0402WGF100JTCE"))
    )
    (comp (ref "R33")
      (value "10R")
      (footprint "R_0402")
      (description "R - RESISTOR - SMD - 10R - 1% - 0402")
      (fields (field (name "LCSC PART #") "C25077") (field (name "Comment") "0402WGF100JTCE"))
      (libsource (lib "JLC_PCB") (part "0402WGF100JTCE"))
    )
    (comp (ref "R33_a")
      (value "10R")
      (footprint "R_0402")
      (description "R - RESISTOR - SMD - 10R - 1% - 0402")
      (fields (field (name "LCSC PART #") "C25077") (field (name "Comment") "0402WGF100JTCE"))
      (libsource (lib "JLC_PCB") (part "0402WGF100JTCE"))
    )
    (comp (ref "R34")
      (value "220R")
      (footprint "R_0402")
      (description "R - RESISTOR - SMD - 220R - 1% - 0402")
      (fields (field (name "LCSC PART #") "C25091") (field (name "Comment") "0402WGF2200TCE"))
      (libsource (lib "JLC_PCB") (part "0402WGF2200TCE"))
    )
    (comp (ref "R35")
      (value "0R")
      (footprint "R_0402")
      (description "R - RESISTOR - SMD - 0R - 1% - 0402")
      (fields (field (name "LCSC PART #") "C17168") (field (name "Comment") "0402WGF0000TCE"))
      (libsource (lib "JLC_PCB") (part "0402WGF0000TCE"))
    )
    (comp (ref "R36")
      (value "10k")
      (footprint "R_0402")
      (description "R - RESISTOR - SMD - 10k - 1% - 0402")
      (fields (field (name "LCSC PART #") "C25744") (field (name "Comment") "0402WGF1002TCE"))
      (libsource (lib "JLC_PCB") (part "0402WGF1002TCE"))
    )
    (comp (ref "R37")
      (value "0R")
      (footprint "R_0402")
      (description "R - RESISTOR - SMD - 0R - 1% - 0402")
      (fields (field (name "LCSC PART #") "C17168") (field (name "Comment") "0402WGF0000TCE"))
      (libsource (lib "JLC_PCB") (part "0402WGF0000TCE"))
    )
    (comp (ref "R38")
      (value "4.7k")
      (footprint "R_0402")
      (description "R - RESISTOR - SMD - 4.7k - 1% - 0402")
      (fields (field (name "LCSC PART #") "C25900") (field (name "Comment") "0402WGF4701TCE"))
      (libsource (lib "JLC_PCB") (part "0402WGF4701TCE"))
    )
    (comp (ref "R39")
      (value "1M")
      (footprint "R_0402")
      (description "R - RESISTOR - SMD - 1M - 1% - 0402")
      (fields (field (name "LCSC PART #") "C26083") (field (name "Comment") "0402WGF1004TCE"))
      (libsource (lib "JLC_PCB") (part "0402WGF1004TCE"))
    )
    (comp (ref "R40")
      (value "150k")
      (footprint "R_0402")
      (description "R - RESISTOR - SMD - 150k - 1% - 0402")
      (fields (field (name "LCSC PART #") "C25755") (field (name "Comment") "0402WGF1503TCE"))
      (libsource (lib "JLC_PCB") (part "0402WGF1503TCE"))
    )
    (comp (ref "R41")
      (value "100k")
      (footprint "R_0402")
      (description "R - RESISTOR - SMD - 100k - 1% -  0402")
      (fields (field (name "LCSC PART #") "C25741") (field (name "Comment") "0402WGF1003TCE"))
      (libsource (lib "JLC_PCB") (part "0402WGF1003TCE"))
    )
    (comp (ref "R42")
      (value "10k")
      (footprint "R_0402")
      (description "R - RESISTOR - SMD - 10k - 1% - 0402")
      (fields (field (name "LCSC PART #") "C25744") (field (name "Comment") "0402WGF1002TCE"))
      (libsource (lib "JLC_PCB") (part "0402WGF1002TCE"))
    )
    (comp (ref "R43")
      (value "10k")
      (footprint "R_0402")
      (description "R - RESISTOR - SMD - 10k - 1% - 0402")
      (fields (field (name "LCSC PART #") "C25744") (field (name "Comment") "0402WGF1002TCE"))
      (libsource (lib "JLC_PCB") (part "0402WGF1002TCE"))
    )
    (comp (ref "R44")
      (value "0R")
      (footprint "R_0402")
      (description "R - RESISTOR - SMD - 0R - 1% - 0402")
      (fields (field (name "LCSC PART #") "C17168") (field (name "Comment") "0402WGF0000TCE"))
      (libsource (lib "JLC_PCB") (part "0402WGF0000TCE"))
    )
    (comp (ref "R45")
      (value "10k")
      (footprint "R_0402")
      (description "R - RESISTOR - SMD - 10k - 1% - 0402")
      (fields (field (name "LCSC PART #") "C25744") (field (name "Comment") "0402WGF1002TCE"))
      (libsource (lib "JLC_PCB") (part "0402WGF1002TCE"))
    )
    (comp (ref "R47")
      (value "10k")
      (footprint "R_0402")
      (description "R - RESISTOR - SMD - 10k - 1% - 0402")
      (fields (field (name "LCSC PART #") "C25744") (field (name "Comment") "0402WGF1002TCE"))
      (libsource (lib "JLC_PCB") (part "0402WGF1002TCE"))
    )
    (comp (ref "R48")
      (value "10k")
      (footprint "R_0402")
      (description "R - RESISTOR - SMD - 10k - 1% - 0402")
      (fields (field (name "LCSC PART #") "C25744") (field (name "Comment") "0402WGF1002TCE"))
      (libsource (lib "JLC_PCB") (part "0402WGF1002TCE"))
    )
    (comp (ref "R51")
      (value "100k")
      (footprint "R_0603")
      (description "R - RESISTOR - SMD - 100k - 1% -  0603")
      (fields (field (name "LCSC PART #") "C22936") (field (name "Comment") "0603WAF100KT5E"))
      (libsource (lib "JLC_PCB") (part "0603WAF100KT5E"))
    )
    (comp (ref "R53")
      (value "4.7k")
      (footprint "R_0402")
      (description "R - RESISTOR - SMD - 4.7k - 1% - 0402")
      (fields (field (name "LCSC PART #") "C25900") (field (name "Comment") "0402WGF4701TCE"))
      (libsource (lib "JLC_PCB") (part "0402WGF4701TCE"))
    )
    (comp (ref "R56")
      (value "47k")
      (footprint "R_0402")
      (description "R - RESISTOR - SMD - 47k - 1% - 0402")
      (fields (field (name "LCSC PART #") "C25792") (field (name "Comment") "0402WGF4702TCE"))
      (libsource (lib "JLC_PCB") (part "0402WGF4702TCE"))
    )
    (comp (ref "R87_a")
      (value "47k")
      (footprint "R_0402")
      (description "R - RESISTOR - SMD - 47k - 1% - 0402")
      (fields (field (name "LCSC PART #") "C25792") (field (name "Comment") "0402WGF4702TCE"))
      (libsource (lib "JLC_PCB") (part "0402WGF4702TCE"))
    )
    (comp (ref "R100")
      (value "1k")
      (footprint "R_0402")
      (description "R - RESISTOR - SMD - 1k - 1% - 0402")
      (fields (field (name "LCSC PART #") "C11702") (field (name "Comment") "0402WGF1001TCE"))
      (libsource (lib "JLC_PCB") (part "0402WGF1001TCE"))
    )
    (comp (ref "R101")
      (value "1k")
      (footprint "R_0402")
      (description "R - RESISTOR - SMD - 1k - 1% - 0402")
      (fields (field (name "LCSC PART #") "C11702") (field (name "Comment") "0402WGF1001TCE"))
      (libsource (lib "JLC_PCB") (part "0402WGF1001TCE"))
    )
    (comp (ref "R102")
      (value "1k")
      (footprint "R_0402")
      (description "R - RESISTOR - SMD - 1k - 1% - 0402")
      (fields (field (name "LCSC PART #") "C11702") (field (name "Comment") "0402WGF1001TCE"))
      (libsource (lib "JLC_PCB") (part "0402WGF1001TCE"))
    )
    (comp (ref "R103")
      (value "1k")
      (footprint "R_0402")
      (description "R - RESISTOR - SMD - 1k - 1% - 0402")
      (fields (field (name "LCSC PART #") "C11702") (field (name "Comment") "0402WGF1001TCE"))
      (libsource (lib "JLC_PCB") (part "0402WGF1001TCE"))
    )
    (comp (ref "R116")
      (value "47k")
      (footprint "R_0402")
      (description "R - RESISTOR - SMD - 47k - 1% - 0402")
      (fields (field (name "LCSC PART #") "C25792") (field (name "Comment") "0402WGF4702TCE"))
      (libsource (lib "JLC_PCB") (part "0402WGF4702TCE"))
    )
    (comp (ref "R121")
      (value "10k")
      (footprint "R_0402")
      (description "R - RESISTOR - SMD - 10k - 1% - 0402")
      (fields (field (name "LCSC PART #") "C25744") (field (name "Comment") "0402WGF1002TCE"))
      (libsource (lib "JLC_PCB") (part "0402WGF1002TCE"))
    )
    (comp (ref "RA1_N")
      (value "0R")
      (footprint "R_0402")
      (description "R - RESISTOR - SMD - 0R - 1% - 0402")
      (fields (field (name "LCSC PART #") "C17168") (field (name "Comment") "0402WGF0000TCE"))
      (libsource (lib "JLC_PCB") (part "0402WGF0000TCE"))
    )
    (comp (ref "RA1_P")
      (value "0R")
      (footprint "R_0402")
      (description "R - RESISTOR - SMD - 0R - 1% - 0402")
      (fields (field (name "LCSC PART #") "C17168") (field (name "Comment") "0402WGF0000TCE"))
      (libsource (lib "JLC_PCB") (part "0402WGF0000TCE"))
    )
    (comp (ref "RA2_N")
      (value "0R")
      (footprint "R_0402")
      (description "R - RESISTOR - SMD - 0R - 1% - 0402")
      (fields (field (name "LCSC PART #") "C17168") (field (name "Comment") "0402WGF0000TCE"))
      (libsource (lib "JLC_PCB") (part "0402WGF0000TCE"))
    )
    (comp (ref "RA2_P")
      (value "0R")
      (footprint "R_0402")
      (description "R - RESISTOR - SMD - 0R - 1% - 0402")
      (fields (field (name "LCSC PART #") "C17168") (field (name "Comment") "0402WGF0000TCE"))
      (libsource (lib "JLC_PCB") (part "0402WGF0000TCE"))
    )
    (comp (ref "RB1_N")
      (value "0R")
      (footprint "R_0402")
      (description "R - RESISTOR - SMD - 0R - 1% - 0402")
      (fields (field (name "LCSC PART #") "C17168") (field (name "Comment") "0402WGF0000TCE"))
      (libsource (lib "JLC_PCB") (part "0402WGF0000TCE"))
    )
    (comp (ref "RB1_P")
      (value "0R")
      (footprint "R_0402")
      (description "R - RESISTOR - SMD - 0R - 1% - 0402")
      (fields (field (name "LCSC PART #") "C17168") (field (name "Comment") "0402WGF0000TCE"))
      (libsource (lib "JLC_PCB") (part "0402WGF0000TCE"))
    )
    (comp (ref "RB2_N")
      (value "0R")
      (footprint "R_0402")
      (description "R - RESISTOR - SMD - 0R - 1% - 0402")
      (fields (field (name "LCSC PART #") "C17168") (field (name "Comment") "0402WGF0000TCE"))
      (libsource (lib "JLC_PCB") (part "0402WGF0000TCE"))
    )
    (comp (ref "RB2_P")
      (value "0R")
      (footprint "R_0402")
      (description "R - RESISTOR - SMD - 0R - 1% - 0402")
      (fields (field (name "LCSC PART #") "C17168") (field (name "Comment") "0402WGF0000TCE"))
      (libsource (lib "JLC_PCB") (part "0402WGF0000TCE"))
    )
    (comp (ref "Ron_a")
      (value "100k")
      (footprint "R_0402")
      (description "R - RESISTOR - SMD - 100k - 1% -  0402")
      (fields (field (name "LCSC PART #") "C25741") (field (name "Comment") "0402WGF1003TCE"))
      (libsource (lib "JLC_PCB") (part "0402WGF1003TCE"))
    )
    (comp (ref "Ron_b")
      (value "100k")
      (footprint "R_0402")
      (description "R - RESISTOR - SMD - 100k - 1% -  0402")
      (fields (field (name "LCSC PART #") "C25741") (field (name "Comment") "0402WGF1003TCE"))
      (libsource (lib "JLC_PCB") (part "0402WGF1003TCE"))
    )
    (comp (ref "Ron_c")
      (value "100k")
      (footprint "R_0402")
      (description "R - RESISTOR - SMD - 100k - 1% -  0402")
      (fields (field (name "LCSC PART #") "C25741") (field (name "Comment") "0402WGF1003TCE"))
      (libsource (lib "JLC_PCB") (part "0402WGF1003TCE"))
    )
    (comp (ref "Ron_d")
      (value "100k")
      (footprint "R_0402")
      (description "R - RESISTOR - SMD - 100k - 1% -  0402")
      (fields (field (name "LCSC PART #") "C25741") (field (name "Comment") "0402WGF1003TCE"))
      (libsource (lib "JLC_PCB") (part "0402WGF1003TCE"))
    )
    (comp (ref "R_1A_a")
      (value "47k")
      (footprint "R_0402")
      (description "R - RESISTOR - SMD - 47k - 1% - 0402")
      (fields (field (name "LCSC PART #") "C25792") (field (name "Comment") "0402WGF4702TCE"))
      (libsource (lib "JLC_PCB") (part "0402WGF4702TCE"))
    )
    (comp (ref "R_1A_b")
      (value "47k")
      (footprint "R_0402")
      (description "R - RESISTOR - SMD - 47k - 1% - 0402")
      (fields (field (name "LCSC PART #") "C25792") (field (name "Comment") "0402WGF4702TCE"))
      (libsource (lib "JLC_PCB") (part "0402WGF4702TCE"))
    )
    (comp (ref "R_1A_c")
      (value "100k")
      (footprint "R_0402")
      (description "R - RESISTOR - SMD - 100k - 1% -  0402")
      (fields (field (name "LCSC PART #") "C25741") (field (name "Comment") "0402WGF1003TCE"))
      (libsource (lib "JLC_PCB") (part "0402WGF1003TCE"))
    )
    (comp (ref "R_1B_a")
      (value "47k")
      (footprint "R_0402")
      (description "R - RESISTOR - SMD - 47k - 1% - 0402")
      (fields (field (name "LCSC PART #") "C25792") (field (name "Comment") "0402WGF4702TCE"))
      (libsource (lib "JLC_PCB") (part "0402WGF4702TCE"))
    )
    (comp (ref "R_1B_b")
      (value "47k")
      (footprint "R_0402")
      (description "R - RESISTOR - SMD - 47k - 1% - 0402")
      (fields (field (name "LCSC PART #") "C25792") (field (name "Comment") "0402WGF4702TCE"))
      (libsource (lib "JLC_PCB") (part "0402WGF4702TCE"))
    )
    (comp (ref "R_1B_c")
      (value "100k")
      (footprint "R_0402")
      (description "R - RESISTOR - SMD - 100k - 1% -  0402")
      (fields (field (name "LCSC PART #") "C25741") (field (name "Comment") "0402WGF1003TCE"))
      (libsource (lib "JLC_PCB") (part "0402WGF1003TCE"))
    )
    (comp (ref "R_LEDA_O")
      (value "0R")
      (footprint "R_0402")
      (description "R - RESISTOR - SMD - 0R - 1% - 0402")
      (fields (field (name "LCSC PART #") "C17168") (field (name "Comment") "0402WGF0000TCE"))
      (libsource (lib "JLC_PCB") (part "0402WGF0000TCE"))
    )
    (comp (ref "R_LEDB_O")
      (value "0R")
      (footprint "R_0402")
      (description "R - RESISTOR - SMD - 0R - 1% - 0402")
      (fields (field (name "LCSC PART #") "C17168") (field (name "Comment") "0402WGF0000TCE"))
      (libsource (lib "JLC_PCB") (part "0402WGF0000TCE"))
    )
    (comp (ref "R_SCL3")
      (value "10k")
      (footprint "R_0402")
      (description "R - RESISTOR - SMD - 10k - 1% - 0402")
      (fields (field (name "LCSC PART #") "C25744") (field (name "Comment") "0402WGF1002TCE"))
      (libsource (lib "JLC_PCB") (part "0402WGF1002TCE"))
    )
    (comp (ref "R_SDA3")
      (value "10k")
      (footprint "R_0402")
      (description "R - RESISTOR - SMD - 10k - 1% - 0402")
      (fields (field (name "LCSC PART #") "C25744") (field (name "Comment") "0402WGF1002TCE"))
      (libsource (lib "JLC_PCB") (part "0402WGF1002TCE"))
    )
    (comp (ref "U1")
      (value "LM5008MMX/NOPB")
      (footprint "SOP65P490X110-8N")
      (description "U - IC - BUCK CONVERTER, ADJUSTABLE, 95V, 350mA")
      (libsource (lib "JLC_PCB") (part "LM5008MMX/NOPB"))
    )
    (comp (ref "U5V")
      (value "L78M05ABDT-TR")
      (footprint "TO-252AA")
      (description "U - IC - 5V Power Regulator")
      (fields (field (name "LCSC PART #") "C58069"))
      (libsource (lib "JLC_PCB") (part "L78M05ABDT-TR"))
    )
    (comp (ref "U7")
      (value "SM72295MAX")
      (footprint "M28B_M")
      (description "Photovoltaic Full Bridge Driver")
      (fields (field (name "MANUFACTURER") "National Semiconductor") (field (name "PARTNUMBER") "SM72295"))
      (libsource (lib "SM_ICs") (part "SM72295"))
    )
    (comp (ref "U8")
      (value "SM72442MTE/NOPB")
      (footprint "MTC28_L")
      (description "Programmable Maximum Power Point Tracking Controller for Photovoltaic Solar Panels")
      (fields (field (name "MANUFACTURER") "National Semiconductor") (field (name "PARTNUMBER") "SM72442"))
      (libsource (lib "SM_ICs") (part "SM72442"))
    )
  )
  (nets
    (net (code "1") (name "+5VDC") (class "Default")
      (node (ref "C32") (pin "2") (pinfunction "2_2") (pintype "passive"))
      (node (ref "C34") (pin "2") (pinfunction "2_2") (pintype "passive"))
      (node (ref "C37") (pin "1") (pinfunction "1_1") (pintype "passive"))
      (node (ref "C38") (pin "2") (pinfunction "2_2") (pintype "passive"))
      (node (ref "C42") (pin "2") (pinfunction "2_2") (pintype "passive"))
      (node (ref "R100") (pin "1") (pinfunction "1_1") (pintype "passive"))
      (node (ref "R101") (pin "1") (pinfunction "1_1") (pintype "passive"))
      (node (ref "R102") (pin "1") (pinfunction "1_1") (pintype "passive"))
      (node (ref "R103") (pin "1") (pinfunction "1_1") (pintype "passive"))
      (node (ref "R17") (pin "2") (pinfunction "2_2") (pintype "passive"))
      (node (ref "R21") (pin "2") (pinfunction "2_2") (pintype "passive"))
      (node (ref "R26") (pin "2") (pinfunction "2_2") (pintype "passive"))
      (node (ref "R28") (pin "2") (pinfunction "2_2") (pintype "passive"))
      (node (ref "R29") (pin "2") (pinfunction "2_2") (pintype "passive"))
      (node (ref "R30") (pin "1") (pinfunction "1_1") (pintype "passive"))
      (node (ref "R31") (pin "2") (pinfunction "2_2") (pintype "passive"))
      (node (ref "R36") (pin "1") (pinfunction "1_1") (pintype "passive"))
      (node (ref "R45") (pin "1") (pinfunction "1_1") (pintype "passive"))
      (node (ref "R47") (pin "2") (pinfunction "2_2") (pintype "passive"))
      (node (ref "R48") (pin "2") (pinfunction "2_2") (pintype "passive"))
      (node (ref "R87_a") (pin "2") (pinfunction "2_2") (pintype "passive"))
      (node (ref "U7") (pin "17") (pinfunction "VDD_17") (pintype "power_in"))
      (node (ref "U8") (pin "3") (pinfunction "VDDD_3") (pintype "power_in"))
    )
    (net (code "2") (name "/1A_GATE") (class "Default")
      (node (ref "D_1A") (pin "2") (pinfunction "A_2") (pintype "passive"))
      (node (ref "D_1A_G") (pin "1") (pinfunction "K_1") (pintype "passive"))
      (node (ref "Q_LEDA") (pin "1") (pinfunction "G_1") (pintype "passive"))
      (node (ref "R_1A_b") (pin "2") (pinfunction "2_2") (pintype "passive"))
      (node (ref "R_1A_c") (pin "2") (pinfunction "2_2") (pintype "passive"))
    )
    (net (code "3") (name "/1B_GATE") (class "Default")
      (node (ref "D_1B") (pin "2") (pinfunction "A_2") (pintype "passive"))
      (node (ref "D_1B_G") (pin "1") (pinfunction "K_1") (pintype "passive"))
      (node (ref "R_1B_b") (pin "2") (pinfunction "2_2") (pintype "passive"))
      (node (ref "R_1B_c") (pin "2") (pinfunction "2_2") (pintype "passive"))
    )
    (net (code "4") (name "/3V3_SCL") (class "Default")
      (node (ref "Q_I2C1") (pin "2") (pinfunction "S_2") (pintype "passive"))
      (node (ref "R_SCL3") (pin "1") (pinfunction "1_1") (pintype "passive"))
    )
    (net (code "5") (name "/3V3_SDA") (class "Default")
      (node (ref "Q_I2C2") (pin "2") (pinfunction "S_2") (pintype "passive"))
      (node (ref "R_SDA3") (pin "1") (pinfunction "1_1") (pintype "passive"))
    )
    (net (code "6") (name "/5V_SCL") (class "Default")
      (node (ref "Q_I2C1") (pin "3") (pinfunction "D_3") (pintype "passive"))
      (node (ref "R48") (pin "1") (pinfunction "1_1") (pintype "passive"))
      (node (ref "U8") (pin "8") (pinfunction "SCL_8") (pintype "input"))
    )
    (net (code "7") (name "/5V_SDA") (class "Default")
      (node (ref "Q_I2C2") (pin "3") (pinfunction "D_3") (pintype "passive"))
      (node (ref "R47") (pin "1") (pinfunction "1_1") (pintype "passive"))
      (node (ref "U8") (pin "9") (pinfunction "SDA_9") (pintype "bidirectional"))
    )
    (net (code "8") (name "/A1_N") (class "Default")
      (node (ref "R12") (pin "1") (pinfunction "1_1") (pintype "passive"))
      (node (ref "RA1_P") (pin "2") (pinfunction "2_2") (pintype "passive"))
      (node (ref "RA2_P") (pin "2") (pinfunction "2_2") (pintype "passive"))
    )
    (net (code "9") (name "/A1_P") (class "Default")
      (node (ref "R8") (pin "1") (pinfunction "1_1") (pintype "passive"))
      (node (ref "RA1_N") (pin "2") (pinfunction "2_2") (pintype "passive"))
      (node (ref "RA2_N") (pin "2") (pinfunction "2_2") (pintype "passive"))
    )
    (net (code "10") (name "/A2_N") (class "Default")
      (node (ref "R24_A") (pin "2") (pinfunction "2_2") (pintype "passive"))
      (node (ref "RB1_N") (pin "2") (pinfunction "2_2") (pintype "passive"))
      (node (ref "RB2_N") (pin "2") (pinfunction "2_2") (pintype "passive"))
    )
    (net (code "11") (name "/A2_P") (class "Default")
      (node (ref "R24_B") (pin "2") (pinfunction "2_2") (pintype "passive"))
      (node (ref "RB1_P") (pin "2") (pinfunction "2_2") (pintype "passive"))
      (node (ref "RB2_P") (pin "2") (pinfunction "2_2") (pintype "passive"))
    )
    (net (code "12") (name "/AIIN") (class "Default")
      (node (ref "C58") (pin "2") (pinfunction "2_2") (pintype "passive"))
      (node (ref "R44") (pin "1") (pinfunction "1_1") (pintype "passive"))
      (node (ref "U8") (pin "19") (pinfunction "AIIN_19") (pintype "input"))
    )
    (net (code "13") (name "/AIOUT") (class "Default")
      (node (ref "C60") (pin "2") (pinfunction "2_2") (pintype "passive"))
      (node (ref "R37") (pin "1") (pinfunction "1_1") (pintype "passive"))
      (node (ref "U8") (pin "21") (pinfunction "AIOUT_21") (pintype "output"))
    )
    (net (code "14") (name "/AVIN") (class "Default")
      (node (ref "C29") (pin "2") (pinfunction "2_2") (pintype "passive"))
      (node (ref "R13") (pin "1") (pinfunction "1_1") (pintype "passive"))
      (node (ref "R20") (pin "1") (pinfunction "1_1") (pintype "passive"))
      (node (ref "U8") (pin "15") (pinfunction "AVIN_15") (pintype "input"))
    )
    (net (code "15") (name "/AVOUT") (class "Default")
      (node (ref "C59") (pin "2") (pinfunction "2_2") (pintype "passive"))
      (node (ref "R51") (pin "1") (pinfunction "1_1") (pintype "passive"))
      (node (ref "R53") (pin "1") (pinfunction "1_1") (pintype "passive"))
      (node (ref "U8") (pin "17") (pinfunction "AVOUT_17") (pintype "output"))
    )
    (net (code "16") (name "/BIN") (class "Default")
      (node (ref "R37") (pin "2") (pinfunction "2_2") (pintype "passive"))
      (node (ref "U7") (pin "4") (pinfunction "BIN_4") (pintype "output"))
    )
    (net (code "17") (name "/BOUT") (class "Default")
      (node (ref "R44") (pin "2") (pinfunction "2_2") (pintype "passive"))
      (node (ref "U7") (pin "11") (pinfunction "BOUT_11") (pintype "output"))
    )
    (net (code "18") (name "/GND_OUT") (class "Default")
      (node (ref "J_OUT") (pin "MINUS") (pinfunction "-_MINUS") (pintype "passive"))
      (node (ref "R6") (pin "2") (pinfunction "2_2") (pintype "passive"))
      (node (ref "RA2_P") (pin "1") (pinfunction "1_1") (pintype "passive"))
    )
    (net (code "19") (name "/HIA") (class "Default")
      (node (ref "U7") (pin "7") (pinfunction "HIA_7") (pintype "input"))
      (node (ref "U8") (pin "26") (pinfunction "HIA_26") (pintype "output"))
    )
    (net (code "20") (name "/HIB") (class "Default")
      (node (ref "U7") (pin "8") (pinfunction "HIB_8") (pintype "input"))
      (node (ref "U8") (pin "25") (pinfunction "HIB_25") (pintype "output"))
    )
    (net (code "21") (name "/HO_A") (class "Default")
      (node (ref "D3") (pin "1") (pinfunction "K_1") (pintype "passive"))
      (node (ref "R18") (pin "1") (pinfunction "1_1") (pintype "passive"))
      (node (ref "R18_a") (pin "1") (pinfunction "1_1") (pintype "passive"))
      (node (ref "U7") (pin "27") (pinfunction "HOA_27") (pintype "output"))
    )
    (net (code "22") (name "/HO_B") (class "Default")
      (node (ref "D4") (pin "1") (pinfunction "K_1") (pintype "passive"))
      (node (ref "R19") (pin "2") (pinfunction "2_2") (pintype "passive"))
      (node (ref "R19_a") (pin "2") (pinfunction "2_2") (pintype "passive"))
      (node (ref "U7") (pin "19") (pinfunction "HOB_19") (pintype "output"))
    )
    (net (code "23") (name "/HS_A") (class "Default")
      (node (ref "C18") (pin "2") (pinfunction "2_2") (pintype "passive"))
      (node (ref "C46") (pin "2") (pinfunction "2_2") (pintype "passive"))
      (node (ref "D12") (pin "1") (pinfunction "K_1") (pintype "passive"))
      (node (ref "D13") (pin "2") (pinfunction "A_2") (pintype "passive"))
      (node (ref "L1") (pin "1") (pinfunction "1_1") (pintype "passive"))
      (node (ref "L2") (pin "1") (pinfunction "1_1") (pintype "passive"))
      (node (ref "L3") (pin "1") (pinfunction "1_1") (pintype "passive"))
      (node (ref "L4") (pin "1") (pinfunction "1_1") (pintype "passive"))
      (node (ref "L5") (pin "1") (pinfunction "1_1") (pintype "passive"))
      (node (ref "L6") (pin "1") (pinfunction "1_1") (pintype "passive"))
      (node (ref "L7") (pin "1") (pinfunction "1_1") (pintype "passive"))
      (node (ref "L8") (pin "1") (pinfunction "1_1") (pintype "passive"))
      (node (ref "L9") (pin "1") (pinfunction "1_1") (pintype "passive"))
      (node (ref "Q1") (pin "3") (pinfunction "S_3") (pintype "passive"))
      (node (ref "Q3") (pin "2") (pinfunction "D_2") (pintype "passive"))
      (node (ref "R4") (pin "1") (pinfunction "1_1") (pintype "passive"))
      (node (ref "U7") (pin "28") (pinfunction "HSA_28") (pintype "passive"))
    )
    (net (code "24") (name "/HS_B") (class "Default")
      (node (ref "C19") (pin "2") (pinfunction "2_2") (pintype "passive"))
      (node (ref "C54") (pin "2") (pinfunction "2_2") (pintype "passive"))
      (node (ref "D7") (pin "2") (pinfunction "A_2") (pintype "passive"))
      (node (ref "D9") (pin "1") (pinfunction "K_1") (pintype "passive"))
      (node (ref "L1") (pin "2") (pinfunction "2_2") (pintype "passive"))
      (node (ref "L2") (pin "2") (pinfunction "2_2") (pintype "passive"))
      (node (ref "L3") (pin "2") (pinfunction "2_2") (pintype "passive"))
      (node (ref "L4") (pin "2") (pinfunction "2_2") (pintype "passive"))
      (node (ref "L5") (pin "2") (pinfunction "2_2") (pintype "passive"))
      (node (ref "L6") (pin "2") (pinfunction "2_2") (pintype "passive"))
      (node (ref "L7") (pin "2") (pinfunction "2_2") (pintype "passive"))
      (node (ref "L8") (pin "2") (pinfunction "2_2") (pintype "passive"))
      (node (ref "L9") (pin "2") (pinfunction "2_2") (pintype "passive"))
      (node (ref "Q2") (pin "3") (pinfunction "S_3") (pintype "passive"))
      (node (ref "Q4") (pin "2") (pinfunction "D_2") (pintype "passive"))
      (node (ref "R3") (pin "2") (pinfunction "2_2") (pintype "passive"))
      (node (ref "U7") (pin "18") (pinfunction "HSB_18") (pintype "passive"))
    )
    (net (code "25") (name "/IIN") (class "Default")
      (node (ref "C61") (pin "2") (pinfunction "2_2") (pintype "passive"))
      (node (ref "R56") (pin "2") (pinfunction "2_2") (pintype "passive"))
      (node (ref "U7") (pin "3") (pinfunction "IIN_3") (pintype "output"))
    )
    (net (code "26") (name "/IOUT") (class "Default")
      (node (ref "C62") (pin "2") (pinfunction "2_2") (pintype "passive"))
      (node (ref "R116") (pin "2") (pinfunction "2_2") (pintype "passive"))
      (node (ref "U7") (pin "12") (pinfunction "IOUT_12") (pintype "output"))
    )
    (net (code "27") (name "/LED_A") (class "Default")
      (node (ref "J1") (pin "9") (pinfunction "9_9") (pintype "passive"))
      (node (ref "J2") (pin "11") (pinfunction "11_11") (pintype "passive"))
      (node (ref "R_LEDB_O") (pin "2") (pinfunction "2_2") (pintype "passive"))
    )
    (net (code "28") (name "/LED_B") (class "Default")
      (node (ref "J1") (pin "11") (pinfunction "11_11") (pintype "passive"))
      (node (ref "J2") (pin "9") (pinfunction "9_9") (pintype "passive"))
      (node (ref "R_LEDA_O") (pin "2") (pinfunction "2_2") (pintype "passive"))
    )
    (net (code "29") (name "/LED_VSS") (class "Default")
      (node (ref "Q_LEDA") (pin "2") (pinfunction "S_2") (pintype "passive"))
      (node (ref "Q_LEDB") (pin "2") (pinfunction "S_2") (pintype "passive"))
      (node (ref "Q_LEDVSS") (pin "3") (pinfunction "D_3") (pintype "passive"))
    )
    (net (code "30") (name "/LIA") (class "Default")
      (node (ref "U7") (pin "6") (pinfunction "LIA_6") (pintype "input"))
      (node (ref "U8") (pin "27") (pinfunction "LIA_27") (pintype "output"))
    )
    (net (code "31") (name "/LIB") (class "Default")
      (node (ref "U7") (pin "9") (pinfunction "LIB_9") (pintype "input"))
      (node (ref "U8") (pin "24") (pinfunction "LIB_24") (pintype "output"))
    )
    (net (code "32") (name "/LO_A") (class "Default")
      (node (ref "D5") (pin "1") (pinfunction "K_1") (pintype "passive"))
      (node (ref "R32") (pin "1") (pinfunction "1_1") (pintype "passive"))
      (node (ref "R32_a") (pin "1") (pinfunction "1_1") (pintype "passive"))
      (node (ref "U7") (pin "24") (pinfunction "LOA_24") (pintype "output"))
    )
    (net (code "33") (name "/LO_B") (class "Default")
      (node (ref "D6") (pin "1") (pinfunction "K_1") (pintype "passive"))
      (node (ref "R33") (pin "2") (pinfunction "2_2") (pintype "passive"))
      (node (ref "R33_a") (pin "2") (pinfunction "2_2") (pintype "passive"))
      (node (ref "U7") (pin "22") (pinfunction "LOB_22") (pintype "output"))
    )
    (net (code "34") (name "/NC4") (class "Default")
      (node (ref "C69") (pin "2") (pinfunction "2_2") (pintype "passive"))
      (node (ref "R87_a") (pin "1") (pinfunction "1_1") (pintype "passive"))
      (node (ref "U8") (pin "23") (pinfunction "NC4_23") (pintype "passive"))
    )
    (net (code "35") (name "/OVS") (class "Default")
      (node (ref "R121") (pin "1") (pinfunction "1_1") (pintype "passive"))
      (node (ref "U7") (pin "16") (pinfunction "OVS_16") (pintype "passive"))
    )
    (net (code "36") (name "/PAN_DET") (class "Default")
      (node (ref "D_1A") (pin "1") (pinfunction "K_1") (pintype "passive"))
      (node (ref "D_1B") (pin "1") (pinfunction "K_1") (pintype "passive"))
      (node (ref "Q_LEDVSS") (pin "1") (pinfunction "G_1") (pintype "passive"))
    )
    (net (code "37") (name "/PM") (class "Default")
      (node (ref "U8") (pin "28") (pinfunction "PM_28") (pintype "input"))
    )
    (net (code "38") (name "/RST") (class "Default")
      (node (ref "U7") (pin "10") (pinfunction "PGD_10") (pintype "open_collector"))
    )
    (net (code "39") (name "/SOL_1A") (class "Default")
      (node (ref "D1_a") (pin "2") (pinfunction "A_2") (pintype "passive"))
      (node (ref "D1_b") (pin "2") (pinfunction "A_2") (pintype "passive"))
      (node (ref "D1_c") (pin "2") (pinfunction "A_2") (pintype "passive"))
      (node (ref "D1_d") (pin "2") (pinfunction "A_2") (pintype "passive"))
      (node (ref "D1_e") (pin "2") (pinfunction "A_2") (pintype "passive"))
      (node (ref "D1_f") (pin "2") (pinfunction "A_2") (pintype "passive"))
      (node (ref "D3_a") (pin "1") (pinfunction "K_1") (pintype "passive"))
      (node (ref "D3_b") (pin "1") (pinfunction "K_1") (pintype "passive"))
      (node (ref "D3_c") (pin "1") (pinfunction "K_1") (pintype "passive"))
      (node (ref "D3_d") (pin "1") (pinfunction "K_1") (pintype "passive"))
      (node (ref "D3_e") (pin "1") (pinfunction "K_1") (pintype "passive"))
      (node (ref "D3_f") (pin "1") (pinfunction "K_1") (pintype "passive"))
      (node (ref "J1") (pin "1") (pinfunction "1_1") (pintype "passive"))
      (node (ref "J1") (pin "2") (pinfunction "2_2") (pintype "passive"))
      (node (ref "J1") (pin "3") (pinfunction "3_3") (pintype "passive"))
      (node (ref "J1") (pin "4") (pinfunction "4_4") (pintype "passive"))
      (node (ref "J1") (pin "5") (pinfunction "5_5") (pintype "passive"))
      (node (ref "J1") (pin "6") (pinfunction "6_6") (pintype "passive"))
      (node (ref "J1") (pin "7") (pinfunction "7_7") (pintype "passive"))
      (node (ref "J1") (pin "8") (pinfunction "8_8") (pintype "passive"))
      (node (ref "J_IN") (pin "PLUS") (pinfunction "+_PLUS") (pintype "passive"))
      (node (ref "R_1A_a") (pin "1") (pinfunction "1_1") (pintype "passive"))
    )
    (net (code "40") (name "/SOL_1B") (class "Default")
      (node (ref "D2_a") (pin "2") (pinfunction "A_2") (pintype "passive"))
      (node (ref "D2_b") (pin "2") (pinfunction "A_2") (pintype "passive"))
      (node (ref "D2_c") (pin "2") (pinfunction "A_2") (pintype "passive"))
      (node (ref "D2_d") (pin "2") (pinfunction "A_2") (pintype "passive"))
      (node (ref "D2_e") (pin "2") (pinfunction "A_2") (pintype "passive"))
      (node (ref "D2_f") (pin "2") (pinfunction "A_2") (pintype "passive"))
      (node (ref "D4_a") (pin "1") (pinfunction "K_1") (pintype "passive"))
      (node (ref "D4_b") (pin "1") (pinfunction "K_1") (pintype "passive"))
      (node (ref "D4_c") (pin "1") (pinfunction "K_1") (pintype "passive"))
      (node (ref "D4_d") (pin "1") (pinfunction "K_1") (pintype "passive"))
      (node (ref "D4_e") (pin "1") (pinfunction "K_1") (pintype "passive"))
      (node (ref "D4_f") (pin "1") (pinfunction "K_1") (pintype "passive"))
      (node (ref "J2") (pin "1") (pinfunction "1_1") (pintype "passive"))
      (node (ref "J2") (pin "2") (pinfunction "2_2") (pintype "passive"))
      (node (ref "J2") (pin "3") (pinfunction "3_3") (pintype "passive"))
      (node (ref "J2") (pin "4") (pinfunction "4_4") (pintype "passive"))
      (node (ref "J2") (pin "5") (pinfunction "5_5") (pintype "passive"))
      (node (ref "J2") (pin "6") (pinfunction "6_6") (pintype "passive"))
      (node (ref "J2") (pin "7") (pinfunction "7_7") (pintype "passive"))
      (node (ref "J2") (pin "8") (pinfunction "8_8") (pintype "passive"))
      (node (ref "J_IN") (pin "MINUS") (pinfunction "-_MINUS") (pintype "passive"))
      (node (ref "R_1B_a") (pin "1") (pinfunction "1_1") (pintype "passive"))
    )
    (net (code "41") (name "/VOUT_N") (class "Default")
      (node (ref "J_OUT") (pin "PLUS") (pinfunction "+_PLUS") (pintype "passive"))
      (node (ref "R10") (pin "2") (pinfunction "2_2") (pintype "passive"))
      (node (ref "RA1_N") (pin "1") (pinfunction "1_1") (pintype "passive"))
    )
    (net (code "42") (name "/nRST") (class "Default")
      (node (ref "C66") (pin "2") (pinfunction "2_2") (pintype "passive"))
      (node (ref "R26") (pin "1") (pinfunction "1_1") (pintype "passive"))
      (node (ref "U8") (pin "1") (pinfunction "RST_1") (pintype "input"))
    )
    (net (code "43") (name "10VDC") (class "Default")
      (node (ref "C23_a") (pin "1") (pinfunction "1_1") (pintype "passive"))
      (node (ref "C23_b") (pin "1") (pinfunction "1_1") (pintype "passive"))
      (node (ref "C23_c") (pin "1") (pinfunction "1_1") (pintype "passive"))
      (node (ref "C23_d") (pin "1") (pinfunction "1_1") (pintype "passive"))
      (node (ref "C23_e") (pin "1") (pinfunction "1_1") (pintype "passive"))
      (node (ref "C23_f") (pin "1") (pinfunction "1_1") (pintype "passive"))
      (node (ref "C23_g") (pin "1") (pinfunction "1_1") (pintype "passive"))
      (node (ref "C24") (pin "2") (pinfunction "2_2") (pintype "passive"))
      (node (ref "C31") (pin "1") (pinfunction "1_1") (pintype "passive"))
      (node (ref "C35") (pin "1") (pinfunction "1_1") (pintype "passive"))
      (node (ref "C40") (pin "2") (pinfunction "2_2") (pintype "passive"))
      (node (ref "L0") (pin "2") (pinfunction "2_2") (pintype "passive"))
      (node (ref "R9") (pin "1") (pinfunction "1_1") (pintype "passive"))
      (node (ref "U5V") (pin "1") (pinfunction "VIN_1") (pintype "input"))
      (node (ref "U7") (pin "21") (pinfunction "VCC1_21") (pintype "power_in"))
      (node (ref "U7") (pin "25") (pinfunction "VCC2_25") (pintype "power_in"))
    )
    (net (code "44") (name "AGND") (class "Default")
      (node (ref "C61") (pin "1") (pinfunction "1_1") (pintype "passive"))
      (node (ref "C62") (pin "1") (pinfunction "1_1") (pintype "passive"))
      (node (ref "NT2") (pin "1") (pinfunction "1_1") (pintype "passive"))
      (node (ref "R116") (pin "1") (pinfunction "1_1") (pintype "passive"))
      (node (ref "R56") (pin "1") (pinfunction "1_1") (pintype "passive"))
      (node (ref "U7") (pin "5") (pinfunction "AGND_5") (pintype "power_in"))
      (node (ref "U8") (pin "13") (pinfunction "VSSA_13") (pintype "power_in"))
    )
    (net (code "45") (name "GND") (class "Default")
      (node (ref "C15") (pin "2") (pinfunction "2_2") (pintype "passive"))
      (node (ref "C21") (pin "1") (pinfunction "1_1") (pintype "passive"))
      (node (ref "C22") (pin "1") (pinfunction "1_1") (pintype "passive"))
      (node (ref "C23_a") (pin "2") (pinfunction "2_2") (pintype "passive"))
      (node (ref "C23_b") (pin "2") (pinfunction "2_2") (pintype "passive"))
      (node (ref "C23_c") (pin "2") (pinfunction "2_2") (pintype "passive"))
      (node (ref "C23_d") (pin "2") (pinfunction "2_2") (pintype "passive"))
      (node (ref "C23_e") (pin "2") (pinfunction "2_2") (pintype "passive"))
      (node (ref "C23_f") (pin "2") (pinfunction "2_2") (pintype "passive"))
      (node (ref "C23_g") (pin "2") (pinfunction "2_2") (pintype "passive"))
      (node (ref "C26") (pin "1") (pinfunction "1_1") (pintype "passive"))
      (node (ref "C29") (pin "1") (pinfunction "1_1") (pintype "passive"))
      (node (ref "C31") (pin "2") (pinfunction "2_2") (pintype "passive"))
      (node (ref "C32") (pin "1") (pinfunction "1_1") (pintype "passive"))
      (node (ref "C33") (pin "2") (pinfunction "2_2") (pintype "passive"))
      (node (ref "C34") (pin "1") (pinfunction "1_1") (pintype "passive"))
      (node (ref "C35") (pin "2") (pinfunction "2_2") (pintype "passive"))
      (node (ref "C37") (pin "2") (pinfunction "2_2") (pintype "passive"))
      (node (ref "C38") (pin "1") (pinfunction "1_1") (pintype "passive"))
      (node (ref "C39") (pin "1") (pinfunction "1_1") (pintype "passive"))
      (node (ref "C40") (pin "1") (pinfunction "1_1") (pintype "passive"))
      (node (ref "C42") (pin "1") (pinfunction "1_1") (pintype "passive"))
      (node (ref "C49") (pin "1") (pinfunction "1_1") (pintype "passive"))
      (node (ref "C50") (pin "1") (pinfunction "1_1") (pintype "passive"))
      (node (ref "C51") (pin "1") (pinfunction "1_1") (pintype "passive"))
      (node (ref "C52") (pin "2") (pinfunction "2_2") (pintype "passive"))
      (node (ref "C58") (pin "1") (pinfunction "1_1") (pintype "passive"))
      (node (ref "C59") (pin "1") (pinfunction "1_1") (pintype "passive"))
      (node (ref "C60") (pin "1") (pinfunction "1_1") (pintype "passive"))
      (node (ref "C64") (pin "1") (pinfunction "1_1") (pintype "passive"))
      (node (ref "C66") (pin "1") (pinfunction "1_1") (pintype "passive"))
      (node (ref "C69") (pin "1") (pinfunction "1_1") (pintype "passive"))
      (node (ref "D2") (pin "2") (pinfunction "A_2") (pintype "passive"))
      (node (ref "D_1A_G") (pin "2") (pinfunction "A_2") (pintype "passive"))
      (node (ref "D_1B_G") (pin "2") (pinfunction "A_2") (pintype "passive"))
      (node (ref "NT1") (pin "2") (pinfunction "2_2") (pintype "passive"))
      (node (ref "NT2") (pin "2") (pinfunction "2_2") (pintype "passive"))
      (node (ref "Q_LEDVSS") (pin "2") (pinfunction "S_2") (pintype "passive"))
      (node (ref "R121") (pin "2") (pinfunction "2_2") (pintype "passive"))
      (node (ref "R15") (pin "1") (pinfunction "1_1") (pintype "passive"))
      (node (ref "R20") (pin "2") (pinfunction "2_2") (pintype "passive"))
      (node (ref "R25") (pin "1") (pinfunction "1_1") (pintype "passive"))
      (node (ref "R35") (pin "1") (pinfunction "1_1") (pintype "passive"))
      (node (ref "R38") (pin "1") (pinfunction "1_1") (pintype "passive"))
      (node (ref "R39") (pin "1") (pinfunction "1_1") (pintype "passive"))
      (node (ref "R40") (pin "1") (pinfunction "1_1") (pintype "passive"))
      (node (ref "R41") (pin "1") (pinfunction "1_1") (pintype "passive"))
      (node (ref "R42") (pin "1") (pinfunction "1_1") (pintype "passive"))
      (node (ref "R43") (pin "1") (pinfunction "1_1") (pintype "passive"))
      (node (ref "R53") (pin "2") (pinfunction "2_2") (pintype "passive"))
      (node (ref "R5_a") (pin "1") (pinfunction "1_1") (pintype "passive"))
      (node (ref "R_1A_c") (pin "1") (pinfunction "1_1") (pintype "passive"))
      (node (ref "R_1B_c") (pin "1") (pinfunction "1_1") (pintype "passive"))
      (node (ref "U1") (pin "4") (pinfunction "RTN_4") (pintype "bidirectional"))
      (node (ref "U5V") (pin "2") (pinfunction "GND_2") (pintype "power_in"))
      (node (ref "U7") (pin "23") (pinfunction "PGND_23") (pintype "power_in"))
      (node (ref "U8") (pin "4") (pinfunction "VSSD_4") (pintype "power_in"))
    )
    (net (code "46") (name "GND_IN") (class "Default")
      (node (ref "D3_a") (pin "2") (pinfunction "A_2") (pintype "passive"))
      (node (ref "D3_b") (pin "2") (pinfunction "A_2") (pintype "passive"))
      (node (ref "D3_c") (pin "2") (pinfunction "A_2") (pintype "passive"))
      (node (ref "D3_d") (pin "2") (pinfunction "A_2") (pintype "passive"))
      (node (ref "D3_e") (pin "2") (pinfunction "A_2") (pintype "passive"))
      (node (ref "D3_f") (pin "2") (pinfunction "A_2") (pintype "passive"))
      (node (ref "D4_a") (pin "2") (pinfunction "A_2") (pintype "passive"))
      (node (ref "D4_b") (pin "2") (pinfunction "A_2") (pintype "passive"))
      (node (ref "D4_c") (pin "2") (pinfunction "A_2") (pintype "passive"))
      (node (ref "D4_d") (pin "2") (pinfunction "A_2") (pintype "passive"))
      (node (ref "D4_e") (pin "2") (pinfunction "A_2") (pintype "passive"))
      (node (ref "D4_f") (pin "2") (pinfunction "A_2") (pintype "passive"))
      (node (ref "D_CLAMP_18") (pin "2") (pinfunction "A_2") (pintype "passive"))
      (node (ref "R2") (pin "2") (pinfunction "2_2") (pintype "passive"))
      (node (ref "RB2_N") (pin "1") (pinfunction "1_1") (pintype "passive"))
    )
    (net (code "47") (name "Net-(D2-K)") (class "Default")
      (node (ref "C17") (pin "2") (pinfunction "2_2") (pintype "passive"))
      (node (ref "D2") (pin "1") (pinfunction "K_1") (pintype "passive"))
      (node (ref "L0") (pin "1") (pinfunction "1_1") (pintype "passive"))
      (node (ref "U1") (pin "1") (pinfunction "SW_1") (pintype "bidirectional"))
    )
    (net (code "48") (name "Net-(D3-A)") (class "Default")
      (node (ref "D3") (pin "2") (pinfunction "A_2") (pintype "passive"))
      (node (ref "Q1") (pin "1") (pinfunction "G_1") (pintype "passive"))
      (node (ref "R18") (pin "2") (pinfunction "2_2") (pintype "passive"))
      (node (ref "R18_a") (pin "2") (pinfunction "2_2") (pintype "passive"))
      (node (ref "R4") (pin "2") (pinfunction "2_2") (pintype "passive"))
    )
    (net (code "49") (name "Net-(D4-A)") (class "Default")
      (node (ref "D4") (pin "2") (pinfunction "A_2") (pintype "passive"))
      (node (ref "Q2") (pin "1") (pinfunction "G_1") (pintype "passive"))
      (node (ref "R19") (pin "1") (pinfunction "1_1") (pintype "passive"))
      (node (ref "R19_a") (pin "1") (pinfunction "1_1") (pintype "passive"))
      (node (ref "R3") (pin "1") (pinfunction "1_1") (pintype "passive"))
    )
    (net (code "50") (name "Net-(D5-A)") (class "Default")
      (node (ref "D5") (pin "2") (pinfunction "A_2") (pintype "passive"))
      (node (ref "Q3") (pin "1") (pinfunction "G_1") (pintype "passive"))
      (node (ref "R22") (pin "2") (pinfunction "2_2") (pintype "passive"))
      (node (ref "R32") (pin "2") (pinfunction "2_2") (pintype "passive"))
      (node (ref "R32_a") (pin "2") (pinfunction "2_2") (pintype "passive"))
    )
    (net (code "51") (name "Net-(D6-A)") (class "Default")
      (node (ref "D6") (pin "2") (pinfunction "A_2") (pintype "passive"))
      (node (ref "Q4") (pin "1") (pinfunction "G_1") (pintype "passive"))
      (node (ref "R23") (pin "1") (pinfunction "1_1") (pintype "passive"))
      (node (ref "R33") (pin "1") (pinfunction "1_1") (pintype "passive"))
      (node (ref "R33_a") (pin "1") (pinfunction "1_1") (pintype "passive"))
    )
    (net (code "52") (name "Net-(D14-A)") (class "Default")
      (node (ref "C19") (pin "1") (pinfunction "1_1") (pintype "passive"))
      (node (ref "D14") (pin "2") (pinfunction "A_2") (pintype "passive"))
      (node (ref "R14") (pin "2") (pinfunction "2_2") (pintype "passive"))
    )
    (net (code "53") (name "Net-(D15-A)") (class "Default")
      (node (ref "C18") (pin "1") (pinfunction "1_1") (pintype "passive"))
      (node (ref "D15") (pin "2") (pinfunction "A_2") (pintype "passive"))
      (node (ref "R11") (pin "2") (pinfunction "2_2") (pintype "passive"))
    )
    (net (code "54") (name "Net-(D_CLAMP_1-A)") (class "Default")
      (node (ref "D_CLAMP_1") (pin "2") (pinfunction "A_2") (pintype "passive"))
      (node (ref "D_CLAMP_2") (pin "1") (pinfunction "K_1") (pintype "passive"))
    )
    (net (code "55") (name "Net-(D_CLAMP_2-A)") (class "Default")
      (node (ref "D_CLAMP_2") (pin "2") (pinfunction "A_2") (pintype "passive"))
      (node (ref "D_CLAMP_3") (pin "1") (pinfunction "K_1") (pintype "passive"))
    )
    (net (code "56") (name "Net-(D_CLAMP_3-A)") (class "Default")
      (node (ref "D_CLAMP_3") (pin "2") (pinfunction "A_2") (pintype "passive"))
      (node (ref "D_CLAMP_4") (pin "1") (pinfunction "K_1") (pintype "passive"))
    )
    (net (code "57") (name "Net-(D_CLAMP_4-A)") (class "Default")
      (node (ref "D_CLAMP_4") (pin "2") (pinfunction "A_2") (pintype "passive"))
      (node (ref "D_CLAMP_5") (pin "1") (pinfunction "K_1") (pintype "passive"))
    )
    (net (code "58") (name "Net-(D_CLAMP_5-A)") (class "Default")
      (node (ref "D_CLAMP_5") (pin "2") (pinfunction "A_2") (pintype "passive"))
      (node (ref "D_CLAMP_6") (pin "1") (pinfunction "K_1") (pintype "passive"))
    )
    (net (code "59") (name "Net-(D_CLAMP_6-A)") (class "Default")
      (node (ref "D_CLAMP_6") (pin "2") (pinfunction "A_2") (pintype "passive"))
      (node (ref "D_CLAMP_7") (pin "1") (pinfunction "K_1") (pintype "passive"))
    )
    (net (code "60") (name "Net-(D_CLAMP_7-A)") (class "Default")
      (node (ref "D_CLAMP_7") (pin "2") (pinfunction "A_2") (pintype "passive"))
      (node (ref "D_CLAMP_8") (pin "1") (pinfunction "K_1") (pintype "passive"))
      (node (ref "R16") (pin "2") (pinfunction "2_2") (pintype "passive"))
    )
    (net (code "61") (name "Net-(D_CLAMP_8-A)") (class "Default")
      (node (ref "D_CLAMP_8") (pin "2") (pinfunction "A_2") (pintype "passive"))
      (node (ref "D_CLAMP_9") (pin "1") (pinfunction "K_1") (pintype "passive"))
    )
    (net (code "62") (name "Net-(D_CLAMP_10-A)") (class "Default")
      (node (ref "D_CLAMP_10") (pin "2") (pinfunction "A_2") (pintype "passive"))
      (node (ref "D_CLAMP_11") (pin "1") (pinfunction "K_1") (pintype "passive"))
    )
    (net (code "63") (name "Net-(D_CLAMP_10-K)") (class "Default")
      (node (ref "D_CLAMP_10") (pin "1") (pinfunction "K_1") (pintype "passive"))
      (node (ref "D_CLAMP_9") (pin "2") (pinfunction "A_2") (pintype "passive"))
      (node (ref "R16") (pin "1") (pinfunction "1_1") (pintype "passive"))
    )
    (net (code "64") (name "Net-(D_CLAMP_11-A)") (class "Default")
      (node (ref "D_CLAMP_11") (pin "2") (pinfunction "A_2") (pintype "passive"))
      (node (ref "D_CLAMP_12") (pin "1") (pinfunction "K_1") (pintype "passive"))
    )
    (net (code "65") (name "Net-(D_CLAMP_12-A)") (class "Default")
      (node (ref "D_CLAMP_12") (pin "2") (pinfunction "A_2") (pintype "passive"))
      (node (ref "D_CLAMP_13") (pin "1") (pinfunction "K_1") (pintype "passive"))
    )
    (net (code "66") (name "Net-(D_CLAMP_13-A)") (class "Default")
      (node (ref "D_CLAMP_13") (pin "2") (pinfunction "A_2") (pintype "passive"))
      (node (ref "D_CLAMP_14") (pin "1") (pinfunction "K_1") (pintype "passive"))
    )
    (net (code "67") (name "Net-(D_CLAMP_14-A)") (class "Default")
      (node (ref "D_CLAMP_14") (pin "2") (pinfunction "A_2") (pintype "passive"))
      (node (ref "D_CLAMP_15") (pin "1") (pinfunction "K_1") (pintype "passive"))
    )
    (net (code "68") (name "Net-(D_CLAMP_15-A)") (class "Default")
      (node (ref "D_CLAMP_15") (pin "2") (pinfunction "A_2") (pintype "passive"))
      (node (ref "D_CLAMP_16") (pin "1") (pinfunction "K_1") (pintype "passive"))
    )
    (net (code "69") (name "Net-(D_CLAMP_16-A)") (class "Default")
      (node (ref "D_CLAMP_16") (pin "2") (pinfunction "A_2") (pintype "passive"))
      (node (ref "D_CLAMP_17") (pin "1") (pinfunction "K_1") (pintype "passive"))
    )
    (net (code "70") (name "Net-(D_CLAMP_17-A)") (class "Default")
      (node (ref "D_CLAMP_17") (pin "2") (pinfunction "A_2") (pintype "passive"))
      (node (ref "D_CLAMP_18") (pin "1") (pinfunction "K_1") (pintype "passive"))
    )
    (net (code "71") (name "Net-(J1-Pad10)") (class "Default")
      (node (ref "J1") (pin "10") (pinfunction "10_10") (pintype "passive"))
      (node (ref "R101") (pin "2") (pinfunction "2_2") (pintype "passive"))
    )
    (net (code "72") (name "Net-(J1-Pad12)") (class "Default")
      (node (ref "J1") (pin "12") (pinfunction "12_12") (pintype "passive"))
      (node (ref "R100") (pin "2") (pinfunction "2_2") (pintype "passive"))
    )
    (net (code "73") (name "Net-(J1-SHIELD-PadS1)") (class "Default")
      (node (ref "J1") (pin "S1") (pinfunction "SHIELD_S1") (pintype "passive"))
      (node (ref "J1") (pin "S2") (pinfunction "SHIELD_S2") (pintype "passive"))
    )
    (net (code "74") (name "Net-(J2-Pad10)") (class "Default")
      (node (ref "J2") (pin "10") (pinfunction "10_10") (pintype "passive"))
      (node (ref "R102") (pin "2") (pinfunction "2_2") (pintype "passive"))
    )
    (net (code "75") (name "Net-(J2-Pad12)") (class "Default")
      (node (ref "J2") (pin "12") (pinfunction "12_12") (pintype "passive"))
      (node (ref "R103") (pin "2") (pinfunction "2_2") (pintype "passive"))
    )
    (net (code "76") (name "Net-(J2-SHIELD-PadS1)") (class "Default")
      (node (ref "J2") (pin "S1") (pinfunction "SHIELD_S1") (pintype "passive"))
      (node (ref "J2") (pin "S2") (pinfunction "SHIELD_S2") (pintype "passive"))
    )
    (net (code "77") (name "Net-(Q_LEDA-D)") (class "Default")
      (node (ref "Q_LEDA") (pin "3") (pinfunction "D_3") (pintype "passive"))
      (node (ref "Q_LEDB") (pin "1") (pinfunction "G_1") (pintype "passive"))
      (node (ref "R_LEDB_O") (pin "1") (pinfunction "1_1") (pintype "passive"))
    )
    (net (code "78") (name "Net-(Q_LEDB-D)") (class "Default")
      (node (ref "Q_LEDB") (pin "3") (pinfunction "D_3") (pintype "passive"))
      (node (ref "R_LEDA_O") (pin "1") (pinfunction "1_1") (pintype "passive"))
    )
    (net (code "79") (name "Net-(R5-Pad1)") (class "Default")
      (node (ref "R5") (pin "1") (pinfunction "1_1") (pintype "passive"))
      (node (ref "R5_a") (pin "2") (pinfunction "2_2") (pintype "passive"))
    )
    (net (code "80") (name "Net-(R8-Pad2)") (class "Default")
      (node (ref "R8") (pin "2") (pinfunction "2_2") (pintype "passive"))
      (node (ref "R8_A") (pin "1") (pinfunction "1_1") (pintype "passive"))
    )
    (net (code "81") (name "Net-(R12-Pad2)") (class "Default")
      (node (ref "R12") (pin "2") (pinfunction "2_2") (pintype "passive"))
      (node (ref "R12_A") (pin "1") (pinfunction "1_1") (pintype "passive"))
    )
    (net (code "82") (name "Net-(R24-Pad2)") (class "Default")
      (node (ref "R24") (pin "2") (pinfunction "2_2") (pintype "passive"))
      (node (ref "R24_A") (pin "1") (pinfunction "1_1") (pintype "passive"))
    )
    (net (code "83") (name "Net-(R24_B-Pad1)") (class "Default")
      (node (ref "R24_B") (pin "1") (pinfunction "1_1") (pintype "passive"))
      (node (ref "R34") (pin "2") (pinfunction "2_2") (pintype "passive"))
    )
    (net (code "84") (name "Net-(R_1A_a-Pad2)") (class "Default")
      (node (ref "R_1A_a") (pin "2") (pinfunction "2_2") (pintype "passive"))
      (node (ref "R_1A_b") (pin "1") (pinfunction "1_1") (pintype "passive"))
    )
    (net (code "85") (name "Net-(R_1B_a-Pad2)") (class "Default")
      (node (ref "R_1B_a") (pin "2") (pinfunction "2_2") (pintype "passive"))
      (node (ref "R_1B_b") (pin "1") (pinfunction "1_1") (pintype "passive"))
    )
    (net (code "86") (name "Net-(Ron_a-Pad1)") (class "Default")
      (node (ref "Ron_a") (pin "1") (pinfunction "1_1") (pintype "passive"))
      (node (ref "Ron_b") (pin "1") (pinfunction "1_1") (pintype "passive"))
    )
    (net (code "87") (name "Net-(Ron_b-Pad2)") (class "Default")
      (node (ref "Ron_b") (pin "2") (pinfunction "2_2") (pintype "passive"))
      (node (ref "Ron_c") (pin "2") (pinfunction "2_2") (pintype "passive"))
      (node (ref "Ron_d") (pin "2") (pinfunction "2_2") (pintype "passive"))
    )
    (net (code "88") (name "Net-(U1-BST)") (class "Default")
      (node (ref "C17") (pin "1") (pinfunction "1_1") (pintype "passive"))
      (node (ref "U1") (pin "2") (pinfunction "BST_2") (pintype "bidirectional"))
    )
    (net (code "89") (name "Net-(U1-FB)") (class "Default")
      (node (ref "C24") (pin "1") (pinfunction "1_1") (pintype "passive"))
      (node (ref "R15") (pin "2") (pinfunction "2_2") (pintype "passive"))
      (node (ref "R9") (pin "2") (pinfunction "2_2") (pintype "passive"))
      (node (ref "U1") (pin "5") (pinfunction "FB_5") (pintype "bidirectional"))
    )
    (net (code "90") (name "Net-(U1-RCL)") (class "Default")
      (node (ref "R5") (pin "2") (pinfunction "2_2") (pintype "passive"))
      (node (ref "U1") (pin "3") (pinfunction "RCL_3") (pintype "input"))
    )
    (net (code "91") (name "Net-(U1-RT{slash}SD)") (class "Default")
      (node (ref "Ron_a") (pin "2") (pinfunction "2_2") (pintype "passive"))
      (node (ref "U1") (pin "6") (pinfunction "RT/SD_6") (pintype "input"))
    )
    (net (code "92") (name "Net-(U1-VCC)") (class "Default")
      (node (ref "C15") (pin "1") (pinfunction "1_1") (pintype "passive"))
      (node (ref "U1") (pin "7") (pinfunction "VCC_7") (pintype "power_in"))
    )
    (net (code "93") (name "Net-(U5V-Vout)") (class "Default")
      (node (ref "R17") (pin "1") (pinfunction "1_1") (pintype "passive"))
      (node (ref "U5V") (pin "3") (pinfunction "Vout_3") (pintype "output"))
    )
    (net (code "94") (name "Net-(U7-HBA)") (class "Default")
      (node (ref "C46") (pin "1") (pinfunction "1_1") (pintype "passive"))
      (node (ref "U7") (pin "26") (pinfunction "HBA_26") (pintype "passive"))
    )
    (net (code "95") (name "Net-(U7-HBB)") (class "Default")
      (node (ref "C54") (pin "1") (pinfunction "1_1") (pintype "passive"))
      (node (ref "U7") (pin "20") (pinfunction "HBB_20") (pintype "passive"))
    )
    (net (code "96") (name "Net-(U7-SDA)") (class "Default")
      (node (ref "R8_A") (pin "2") (pinfunction "2_2") (pintype "passive"))
      (node (ref "U7") (pin "2") (pinfunction "SDA_2") (pintype "input"))
    )
    (net (code "97") (name "Net-(U7-SIA)") (class "Default")
      (node (ref "R12_A") (pin "2") (pinfunction "2_2") (pintype "passive"))
      (node (ref "U7") (pin "1") (pinfunction "SIA_1") (pintype "input"))
    )
    (net (code "98") (name "Net-(U7-SIB)") (class "Default")
      (node (ref "R24") (pin "1") (pinfunction "1_1") (pintype "passive"))
      (node (ref "U7") (pin "14") (pinfunction "SIB_14") (pintype "input"))
    )
    (net (code "99") (name "Net-(U7-SOB)") (class "Default")
      (node (ref "R34") (pin "1") (pinfunction "1_1") (pintype "passive"))
      (node (ref "U7") (pin "13") (pinfunction "SOB_13") (pintype "output"))
    )
    (net (code "100") (name "Net-(U8-A0)") (class "Default")
      (node (ref "C49") (pin "2") (pinfunction "2_2") (pintype "passive"))
      (node (ref "R28") (pin "1") (pinfunction "1_1") (pintype "passive"))
      (node (ref "R38") (pin "2") (pinfunction "2_2") (pintype "passive"))
      (node (ref "U8") (pin "14") (pinfunction "A0_14") (pintype "bidirectional"))
    )
    (net (code "101") (name "Net-(U8-A2)") (class "Default")
      (node (ref "C50") (pin "2") (pinfunction "2_2") (pintype "passive"))
      (node (ref "R29") (pin "1") (pinfunction "1_1") (pintype "passive"))
      (node (ref "R39") (pin "2") (pinfunction "2_2") (pintype "passive"))
      (node (ref "U8") (pin "16") (pinfunction "A2_16") (pintype "bidirectional"))
    )
    (net (code "102") (name "Net-(U8-A4)") (class "Default")
      (node (ref "C51") (pin "2") (pinfunction "2_2") (pintype "passive"))
      (node (ref "R30") (pin "2") (pinfunction "2_2") (pintype "passive"))
      (node (ref "R40") (pin "2") (pinfunction "2_2") (pintype "passive"))
      (node (ref "U8") (pin "18") (pinfunction "A4_18") (pintype "bidirectional"))
    )
    (net (code "103") (name "Net-(U8-A6)") (class "Default")
      (node (ref "C52") (pin "1") (pinfunction "1_1") (pintype "passive"))
      (node (ref "R31") (pin "1") (pinfunction "1_1") (pintype "passive"))
      (node (ref "R41") (pin "2") (pinfunction "2_2") (pintype "passive"))
      (node (ref "U8") (pin "20") (pinfunction "A6_20") (pintype "bidirectional"))
    )
    (net (code "104") (name "Net-(U8-I2C0)") (class "Default")
      (node (ref "R36") (pin "2") (pinfunction "2_2") (pintype "passive"))
      (node (ref "U8") (pin "6") (pinfunction "I2C0_6") (pintype "bidirectional"))
    )
    (net (code "105") (name "Net-(U8-I2C1)") (class "Default")
      (node (ref "R42") (pin "2") (pinfunction "2_2") (pintype "passive"))
      (node (ref "U8") (pin "7") (pinfunction "I2C1_7") (pintype "bidirectional"))
    )
    (net (code "106") (name "Net-(U8-I2C2)") (class "Default")
      (node (ref "R43") (pin "2") (pinfunction "2_2") (pintype "passive"))
      (node (ref "U8") (pin "22") (pinfunction "I2C2_22") (pintype "bidirectional"))
    )
    (net (code "107") (name "Net-(U8-NC1)") (class "Default")
      (node (ref "R35") (pin "2") (pinfunction "2_2") (pintype "passive"))
      (node (ref "U8") (pin "2") (pinfunction "NC1_2") (pintype "passive"))
    )
    (net (code "108") (name "Net-(U8-NC2)") (class "Default")
      (node (ref "R45") (pin "2") (pinfunction "2_2") (pintype "passive"))
      (node (ref "U8") (pin "5") (pinfunction "NC2_5") (pintype "passive"))
    )
    (net (code "109") (name "Net-(U8-NC3)") (class "Default")
      (node (ref "R25") (pin "2") (pinfunction "2_2") (pintype "passive"))
      (node (ref "U8") (pin "10") (pinfunction "NC3_10") (pintype "passive"))
    )
    (net (code "110") (name "Net-(U8-VDDA)") (class "Default")
      (node (ref "C33") (pin "1") (pinfunction "1_1") (pintype "passive"))
      (node (ref "C39") (pin "2") (pinfunction "2_2") (pintype "passive"))
      (node (ref "R21") (pin "1") (pinfunction "1_1") (pintype "passive"))
      (node (ref "U8") (pin "12") (pinfunction "VDDA_12") (pintype "power_in"))
    )
    (net (code "111") (name "PGND") (class "Default")
      (node (ref "C1") (pin "1") (pinfunction "1_1") (pintype "passive"))
      (node (ref "C10") (pin "1") (pinfunction "1_1") (pintype "passive"))
      (node (ref "C11") (pin "1") (pinfunction "1_1") (pintype "passive"))
      (node (ref "C12") (pin "1") (pinfunction "1_1") (pintype "passive"))
      (node (ref "C13") (pin "1") (pinfunction "1_1") (pintype "passive"))
      (node (ref "C16") (pin "1") (pinfunction "1_1") (pintype "passive"))
      (node (ref "C20") (pin "1") (pinfunction "1_1") (pintype "passive"))
      (node (ref "C25") (pin "1") (pinfunction "1_1") (pintype "passive"))
      (node (ref "C27") (pin "1") (pinfunction "1_1") (pintype "passive"))
      (node (ref "C28") (pin "1") (pinfunction "1_1") (pintype "passive"))
      (node (ref "C30") (pin "1") (pinfunction "1_1") (pintype "passive"))
      (node (ref "C36") (pin "1") (pinfunction "1_1") (pintype "passive"))
      (node (ref "C4") (pin "1") (pinfunction "1_1") (pintype "passive"))
      (node (ref "C41") (pin "1") (pinfunction "1_1") (pintype "passive"))
      (node (ref "C44") (pin "1") (pinfunction "1_1") (pintype "passive"))
      (node (ref "C45") (pin "1") (pinfunction "1_1") (pintype "passive"))
      (node (ref "C47") (pin "1") (pinfunction "1_1") (pintype "passive"))
      (node (ref "C5") (pin "1") (pinfunction "1_1") (pintype "passive"))
      (node (ref "C6") (pin "1") (pinfunction "1_1") (pintype "passive"))
      (node (ref "C7") (pin "1") (pinfunction "1_1") (pintype "passive"))
      (node (ref "C70") (pin "1") (pinfunction "1_1") (pintype "passive"))
      (node (ref "C72") (pin "1") (pinfunction "1_1") (pintype "passive"))
      (node (ref "C8") (pin "1") (pinfunction "1_1") (pintype "passive"))
      (node (ref "C9") (pin "1") (pinfunction "1_1") (pintype "passive"))
      (node (ref "D12") (pin "2") (pinfunction "A_2") (pintype "passive"))
      (node (ref "D14") (pin "1") (pinfunction "K_1") (pintype "passive"))
      (node (ref "D15") (pin "1") (pinfunction "K_1") (pintype "passive"))
      (node (ref "D9") (pin "2") (pinfunction "A_2") (pintype "passive"))
      (node (ref "NT1") (pin "1") (pinfunction "1_1") (pintype "passive"))
      (node (ref "Q3") (pin "3") (pinfunction "S_3") (pintype "passive"))
      (node (ref "Q4") (pin "3") (pinfunction "S_3") (pintype "passive"))
      (node (ref "R11") (pin "1") (pinfunction "1_1") (pintype "passive"))
      (node (ref "R14") (pin "1") (pinfunction "1_1") (pintype "passive"))
      (node (ref "R2") (pin "1") (pinfunction "1_1") (pintype "passive"))
      (node (ref "R22") (pin "1") (pinfunction "1_1") (pintype "passive"))
      (node (ref "R23") (pin "2") (pinfunction "2_2") (pintype "passive"))
      (node (ref "R6") (pin "1") (pinfunction "1_1") (pintype "passive"))
      (node (ref "RA2_N") (pin "1") (pinfunction "1_1") (pintype "passive"))
      (node (ref "RB2_P") (pin "1") (pinfunction "1_1") (pintype "passive"))
    )
    (net (code "112") (name "VCC_3V3") (class "Default")
      (node (ref "Q_I2C1") (pin "1") (pinfunction "G_1") (pintype "passive"))
      (node (ref "Q_I2C2") (pin "1") (pinfunction "G_1") (pintype "passive"))
      (node (ref "R_SCL3") (pin "2") (pinfunction "2_2") (pintype "passive"))
      (node (ref "R_SDA3") (pin "2") (pinfunction "2_2") (pintype "passive"))
    )
    (net (code "113") (name "VIN_N") (class "Default")
      (node (ref "C10") (pin "2") (pinfunction "2_2") (pintype "passive"))
      (node (ref "C11") (pin "2") (pinfunction "2_2") (pintype "passive"))
      (node (ref "C12") (pin "2") (pinfunction "2_2") (pintype "passive"))
      (node (ref "C13") (pin "2") (pinfunction "2_2") (pintype "passive"))
      (node (ref "C4") (pin "2") (pinfunction "2_2") (pintype "passive"))
      (node (ref "C5") (pin "2") (pinfunction "2_2") (pintype "passive"))
      (node (ref "C6") (pin "2") (pinfunction "2_2") (pintype "passive"))
      (node (ref "C7") (pin "2") (pinfunction "2_2") (pintype "passive"))
      (node (ref "C70") (pin "2") (pinfunction "2_2") (pintype "passive"))
      (node (ref "C72") (pin "2") (pinfunction "2_2") (pintype "passive"))
      (node (ref "C8") (pin "2") (pinfunction "2_2") (pintype "passive"))
      (node (ref "C9") (pin "2") (pinfunction "2_2") (pintype "passive"))
      (node (ref "D13") (pin "1") (pinfunction "K_1") (pintype "passive"))
      (node (ref "Q1") (pin "2") (pinfunction "D_2") (pintype "passive"))
      (node (ref "R1") (pin "1") (pinfunction "1_1") (pintype "passive"))
      (node (ref "R13") (pin "2") (pinfunction "2_2") (pintype "passive"))
      (node (ref "RB1_P") (pin "1") (pinfunction "1_1") (pintype "passive"))
    )
    (net (code "114") (name "VIN_P") (class "Default")
      (node (ref "C21") (pin "2") (pinfunction "2_2") (pintype "passive"))
      (node (ref "C22") (pin "2") (pinfunction "2_2") (pintype "passive"))
      (node (ref "C26") (pin "2") (pinfunction "2_2") (pintype "passive"))
      (node (ref "C64") (pin "2") (pinfunction "2_2") (pintype "passive"))
      (node (ref "D1_a") (pin "1") (pinfunction "K_1") (pintype "passive"))
      (node (ref "D1_b") (pin "1") (pinfunction "K_1") (pintype "passive"))
      (node (ref "D1_c") (pin "1") (pinfunction "K_1") (pintype "passive"))
      (node (ref "D1_d") (pin "1") (pinfunction "K_1") (pintype "passive"))
      (node (ref "D1_e") (pin "1") (pinfunction "K_1") (pintype "passive"))
      (node (ref "D1_f") (pin "1") (pinfunction "K_1") (pintype "passive"))
      (node (ref "D2_a") (pin "1") (pinfunction "K_1") (pintype "passive"))
      (node (ref "D2_b") (pin "1") (pinfunction "K_1") (pintype "passive"))
      (node (ref "D2_c") (pin "1") (pinfunction "K_1") (pintype "passive"))
      (node (ref "D2_d") (pin "1") (pinfunction "K_1") (pintype "passive"))
      (node (ref "D2_e") (pin "1") (pinfunction "K_1") (pintype "passive"))
      (node (ref "D2_f") (pin "1") (pinfunction "K_1") (pintype "passive"))
      (node (ref "D_CLAMP_1") (pin "1") (pinfunction "K_1") (pintype "passive"))
      (node (ref "R1") (pin "2") (pinfunction "2_2") (pintype "passive"))
      (node (ref "RB1_N") (pin "1") (pinfunction "1_1") (pintype "passive"))
      (node (ref "Ron_c") (pin "1") (pinfunction "1_1") (pintype "passive"))
      (node (ref "Ron_d") (pin "1") (pinfunction "1_1") (pintype "passive"))
      (node (ref "U1") (pin "8") (pinfunction "VIN_8") (pintype "input"))
    )
    (net (code "115") (name "VOUT_P") (class "Default")
      (node (ref "C1") (pin "2") (pinfunction "2_2") (pintype "passive"))
      (node (ref "C16") (pin "2") (pinfunction "2_2") (pintype "passive"))
      (node (ref "C20") (pin "2") (pinfunction "2_2") (pintype "passive"))
      (node (ref "C25") (pin "2") (pinfunction "2_2") (pintype "passive"))
      (node (ref "C27") (pin "2") (pinfunction "2_2") (pintype "passive"))
      (node (ref "C28") (pin "2") (pinfunction "2_2") (pintype "passive"))
      (node (ref "C30") (pin "2") (pinfunction "2_2") (pintype "passive"))
      (node (ref "C36") (pin "2") (pinfunction "2_2") (pintype "passive"))
      (node (ref "C41") (pin "2") (pinfunction "2_2") (pintype "passive"))
      (node (ref "C44") (pin "2") (pinfunction "2_2") (pintype "passive"))
      (node (ref "C45") (pin "2") (pinfunction "2_2") (pintype "passive"))
      (node (ref "C47") (pin "2") (pinfunction "2_2") (pintype "passive"))
      (node (ref "D7") (pin "1") (pinfunction "K_1") (pintype "passive"))
      (node (ref "Q2") (pin "2") (pinfunction "D_2") (pintype "passive"))
      (node (ref "R10") (pin "1") (pinfunction "1_1") (pintype "passive"))
      (node (ref "R51") (pin "2") (pinfunction "2_2") (pintype "passive"))
      (node (ref "RA1_P") (pin "1") (pinfunction "1_1") (pintype "passive"))
    )
    (net (code "116") (name "unconnected-(J_IN-PadM)") (class "Default")
      (node (ref "J_IN") (pin "M") (pinfunction "M_M") (pintype "passive"))
    )
    (net (code "117") (name "unconnected-(J_OUT-PadM)") (class "Default")
      (node (ref "J_OUT") (pin "M") (pinfunction "M_M") (pintype "passive"))
    )
    (net (code "118") (name "unconnected-(U7-OVP-Pad15)") (class "Default")
      (node (ref "U7") (pin "15") (pinfunction "OVP_15") (pintype "passive"))
    )
    (net (code "119") (name "unconnected-(U8-PM_OUT-Pad11)") (class "Default")
      (node (ref "U8") (pin "11") (pinfunction "PM_OUT_11") (pintype "output"))
    )
  )
)
